# Arm_Board.net
KiCad netlist of a schematic drawn in EAGLE
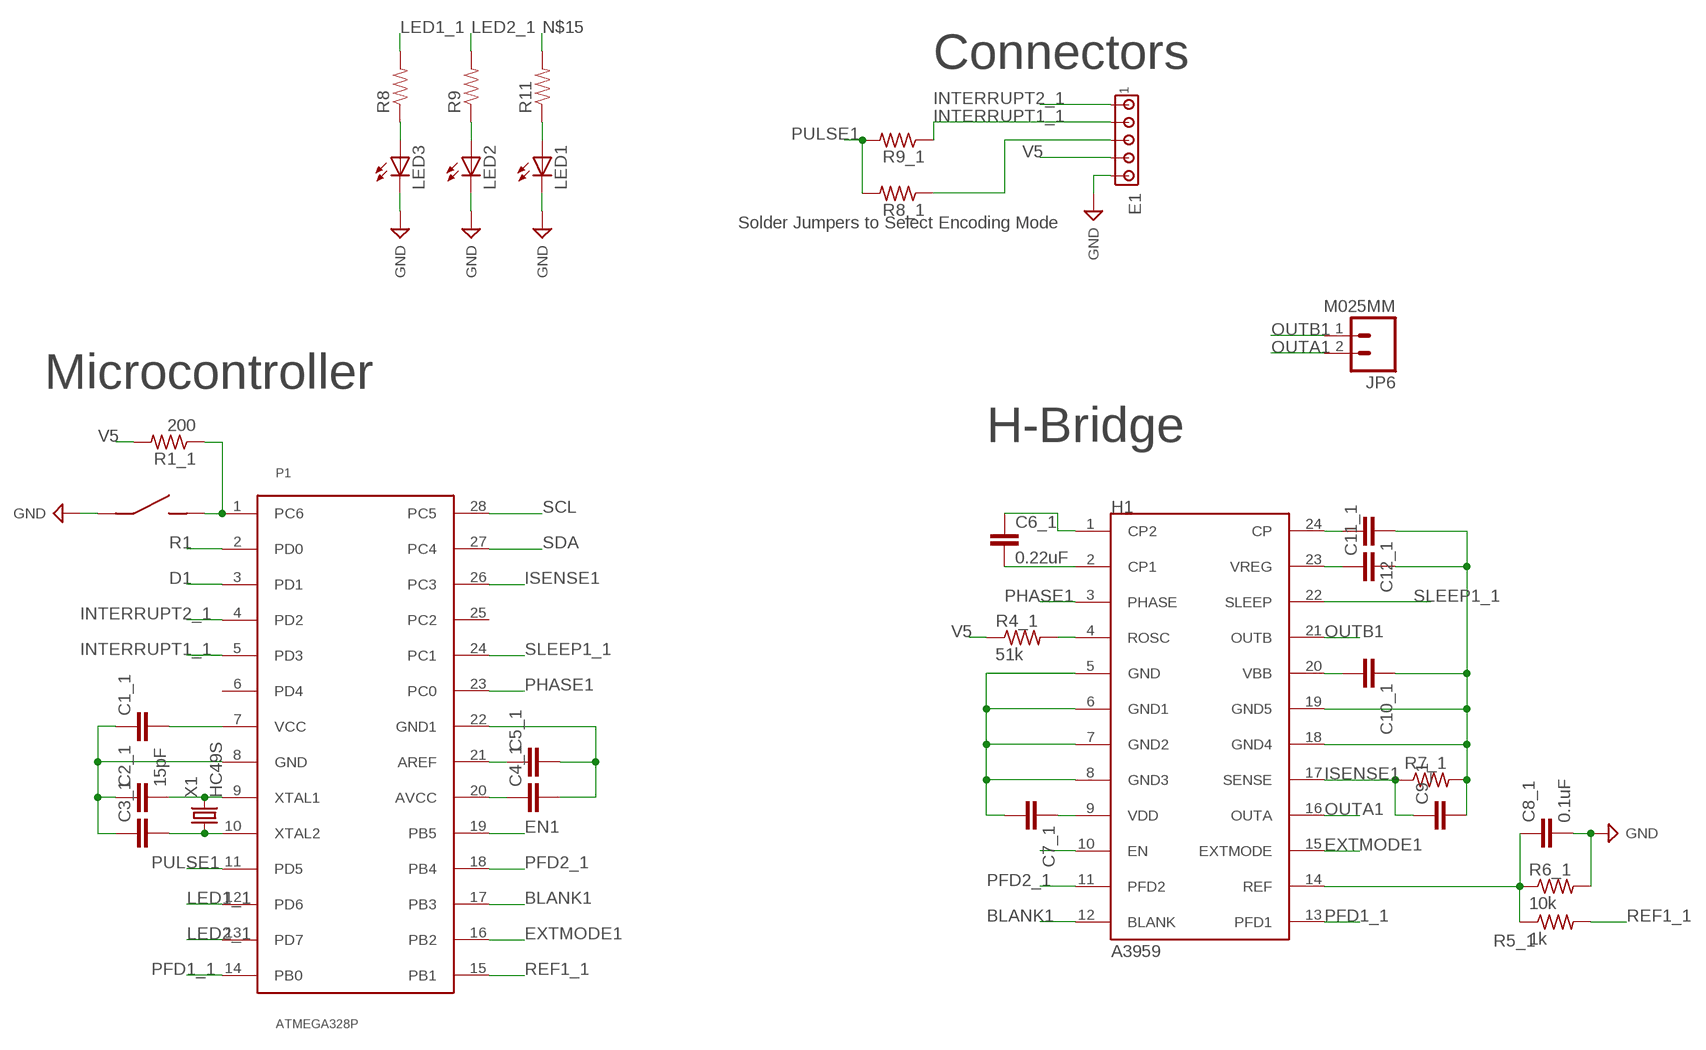
[diagram p0: schematic, sheet 1]
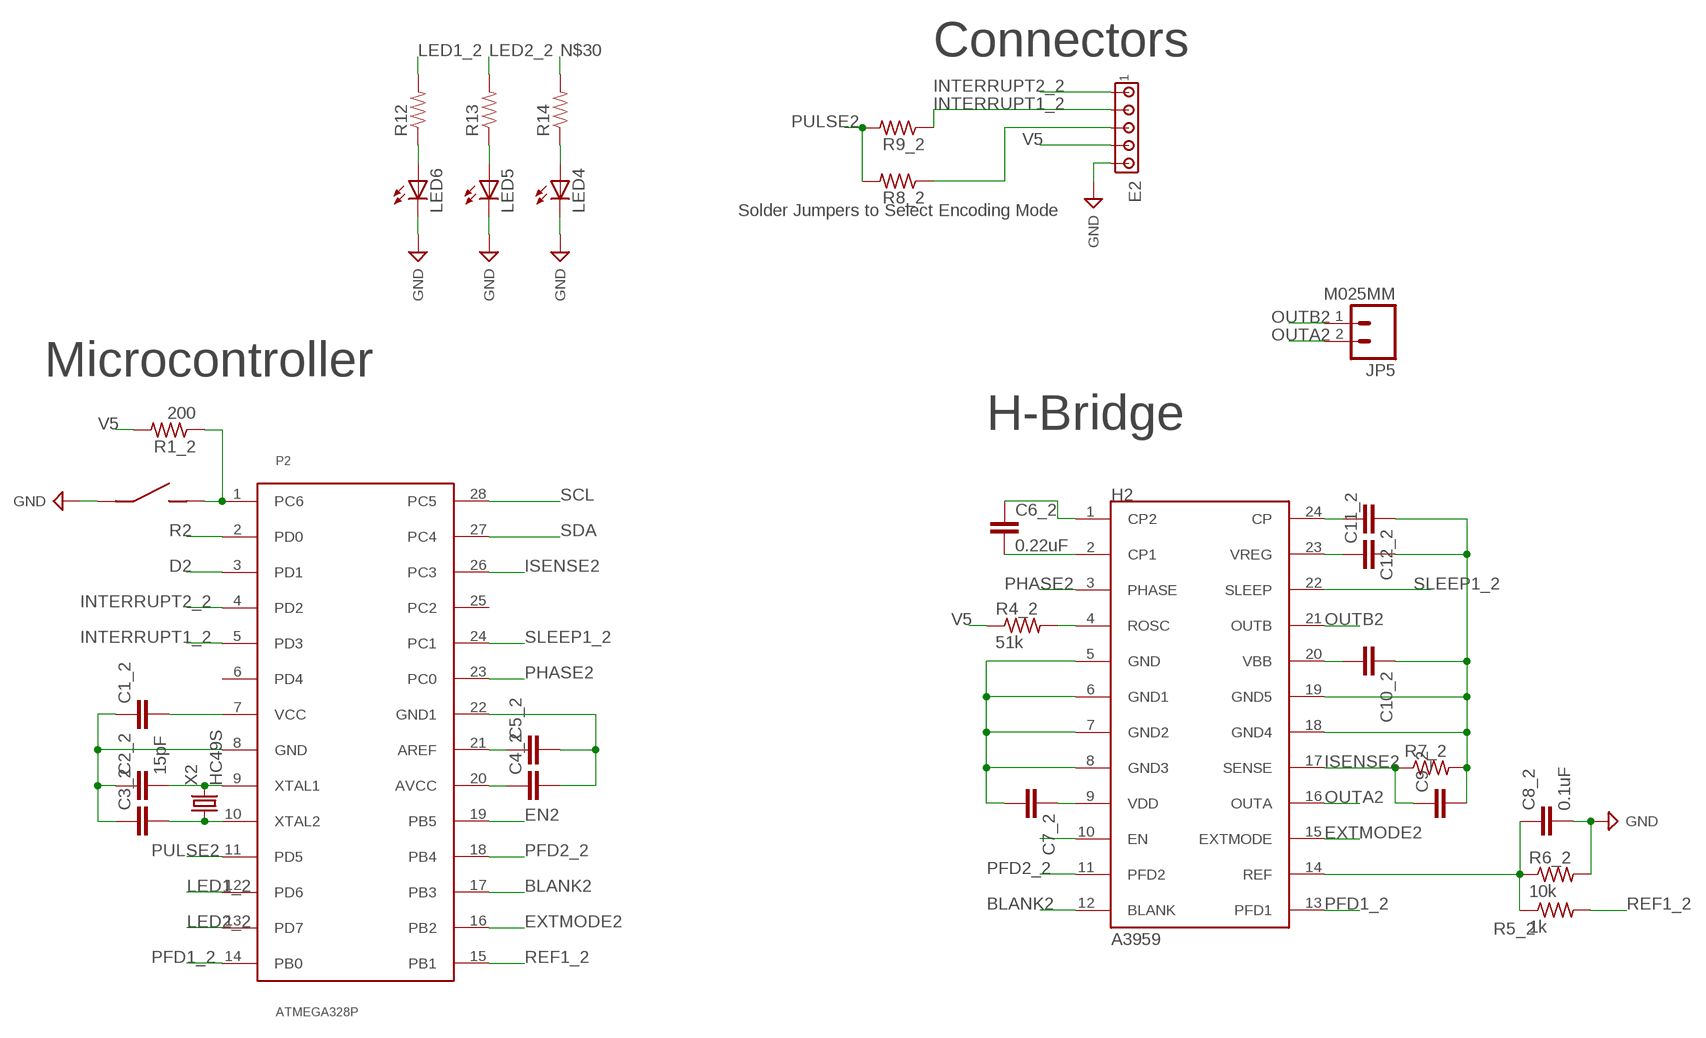
[diagram p1: schematic, sheet 2]
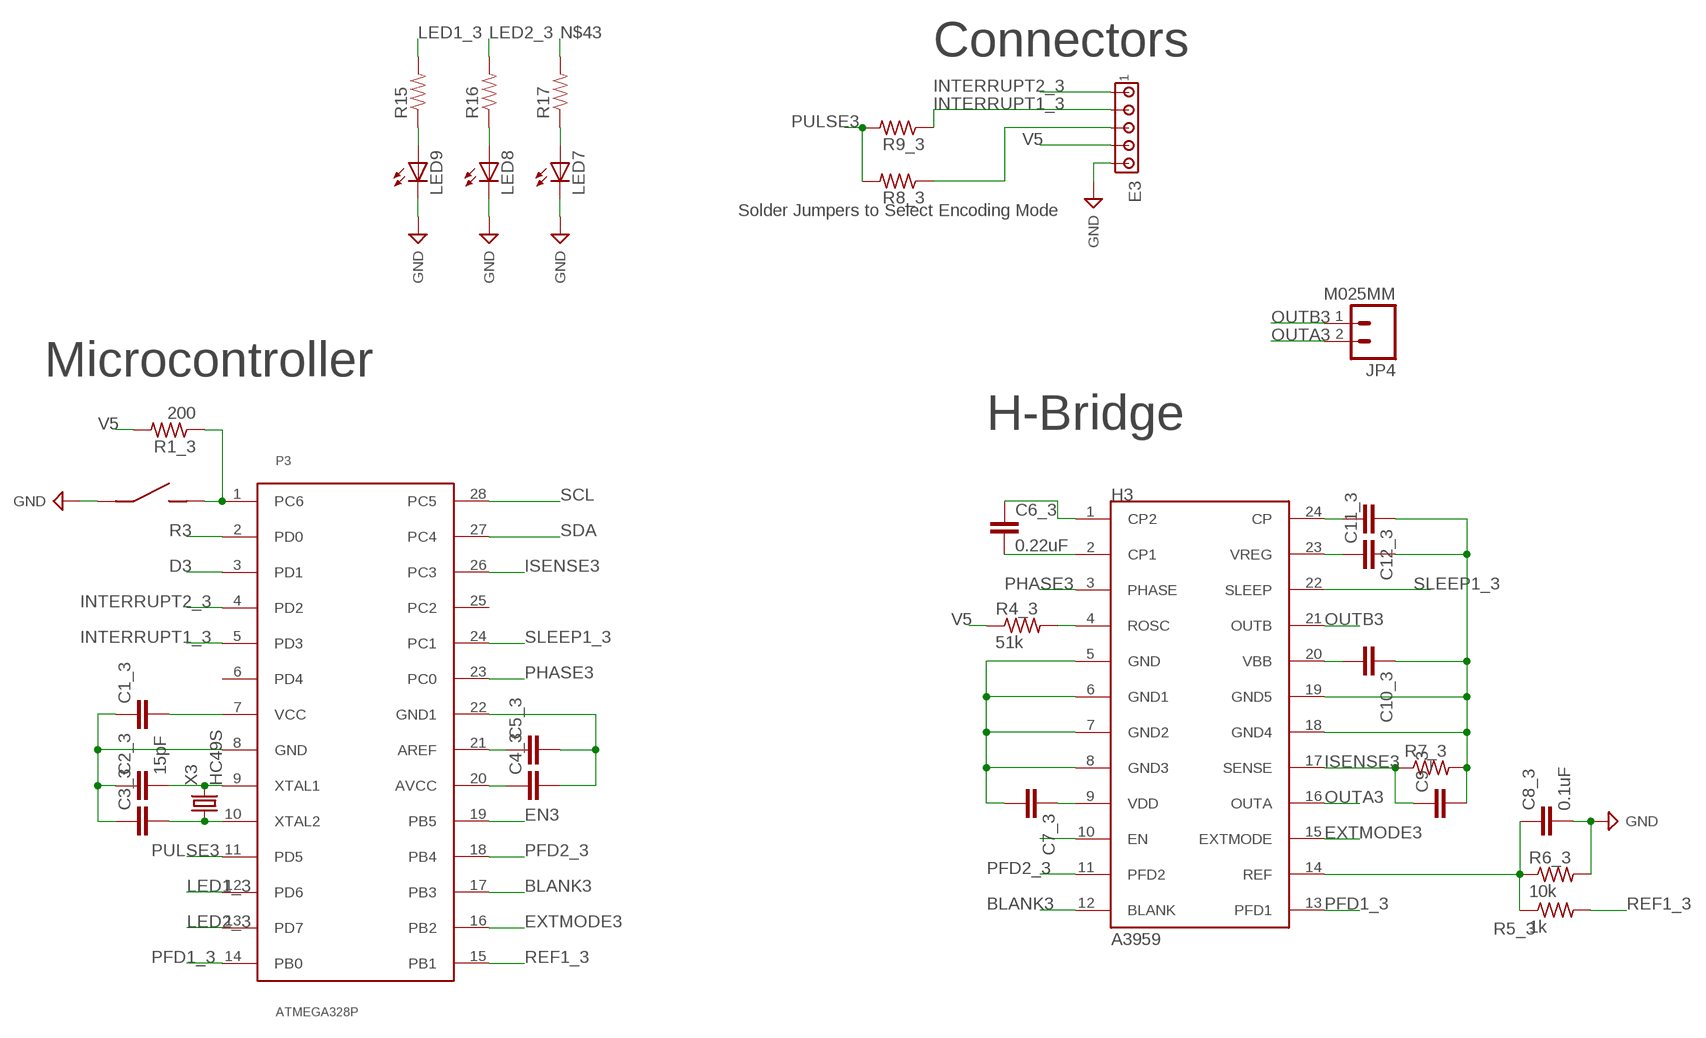
[diagram p2: schematic, sheet 3]
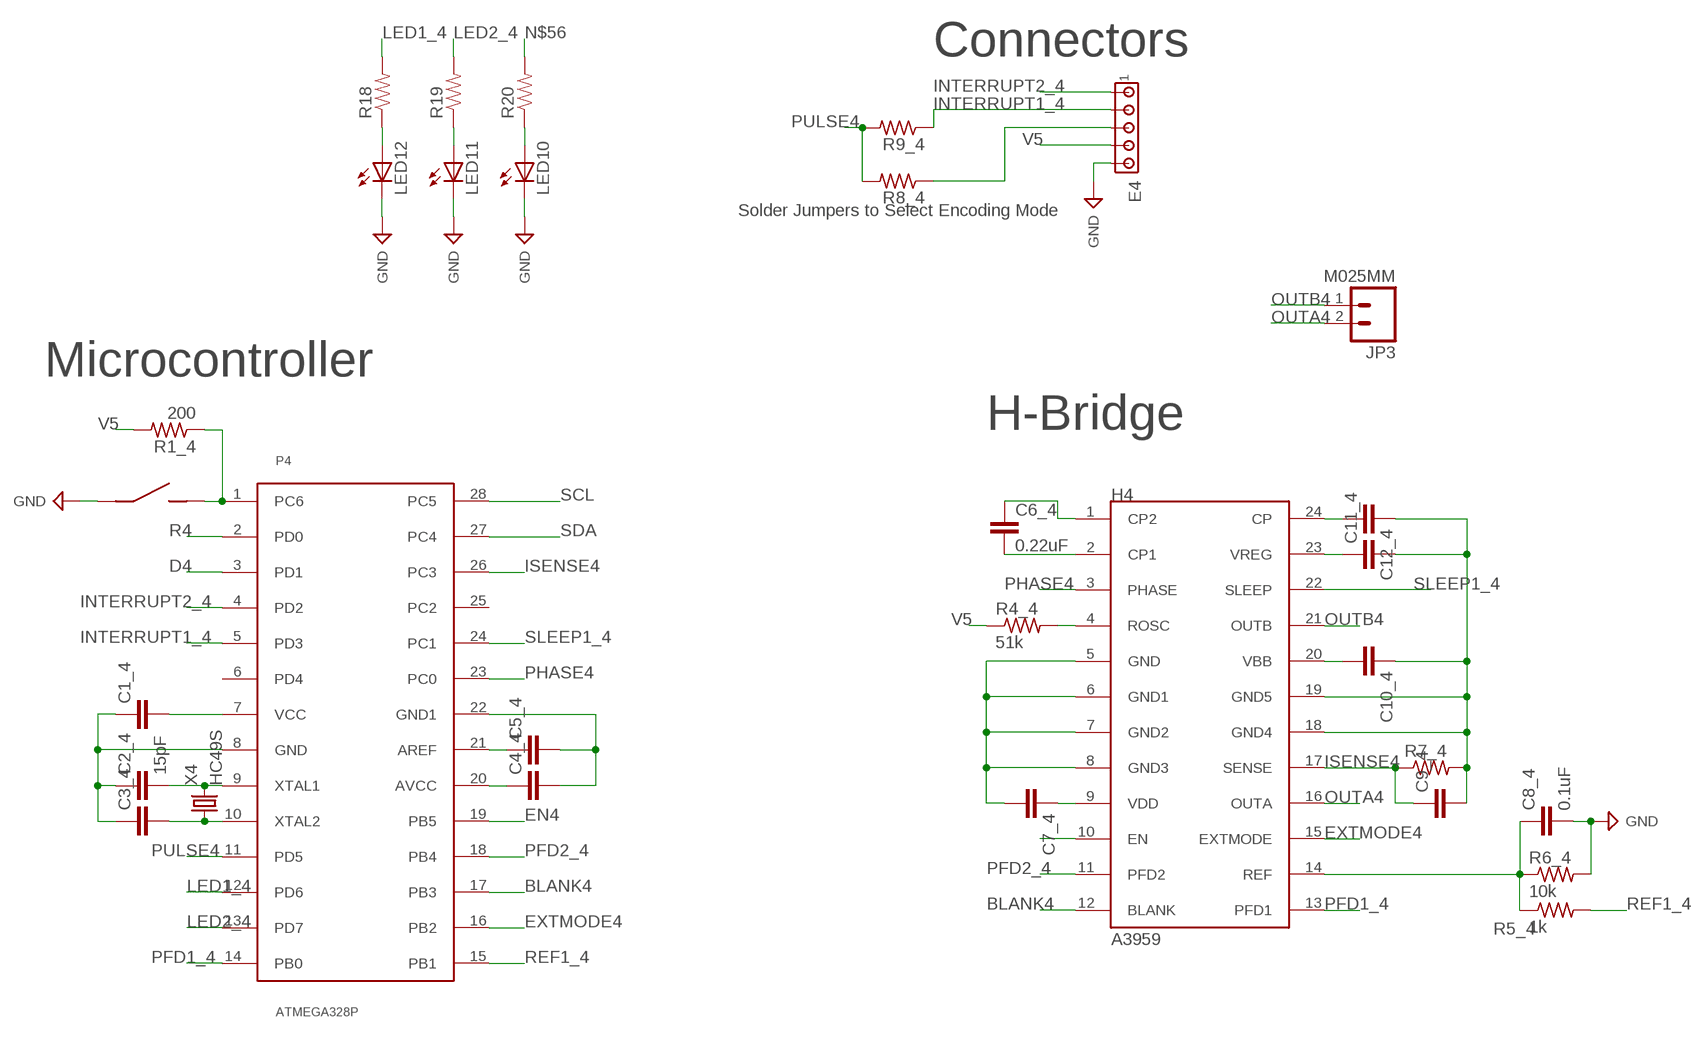
[diagram p3: schematic, sheet 4]
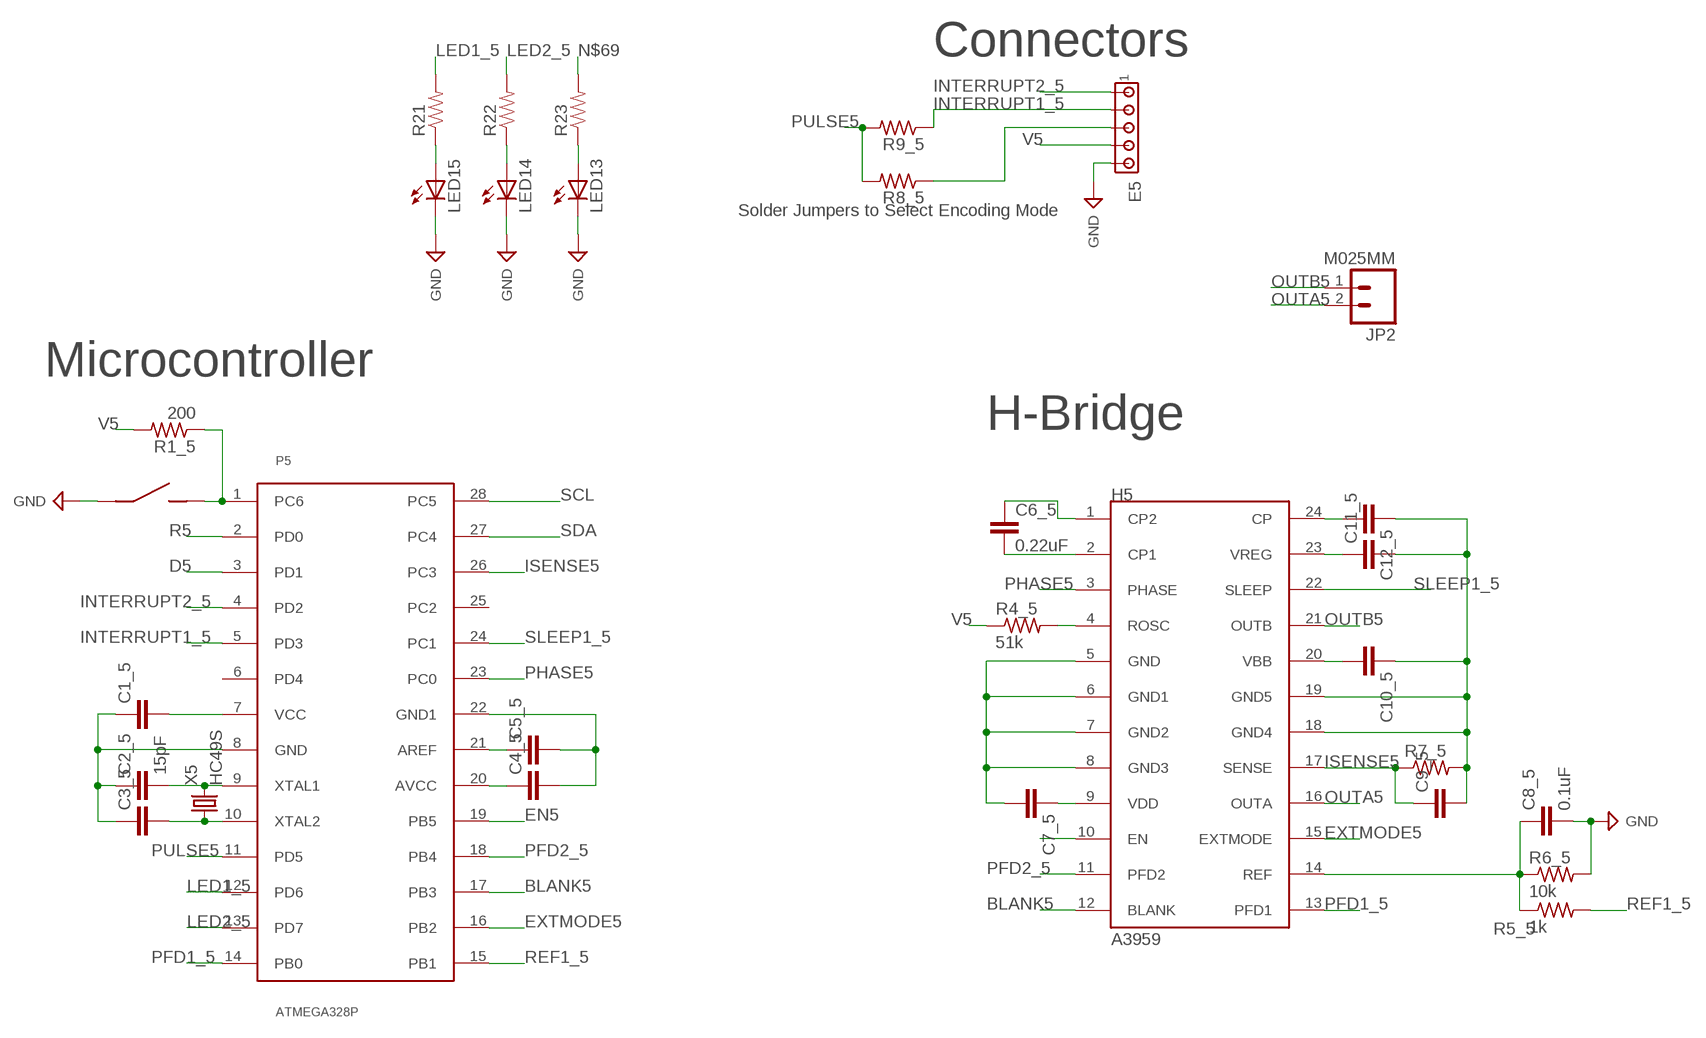
[diagram p4: schematic, sheet 5]
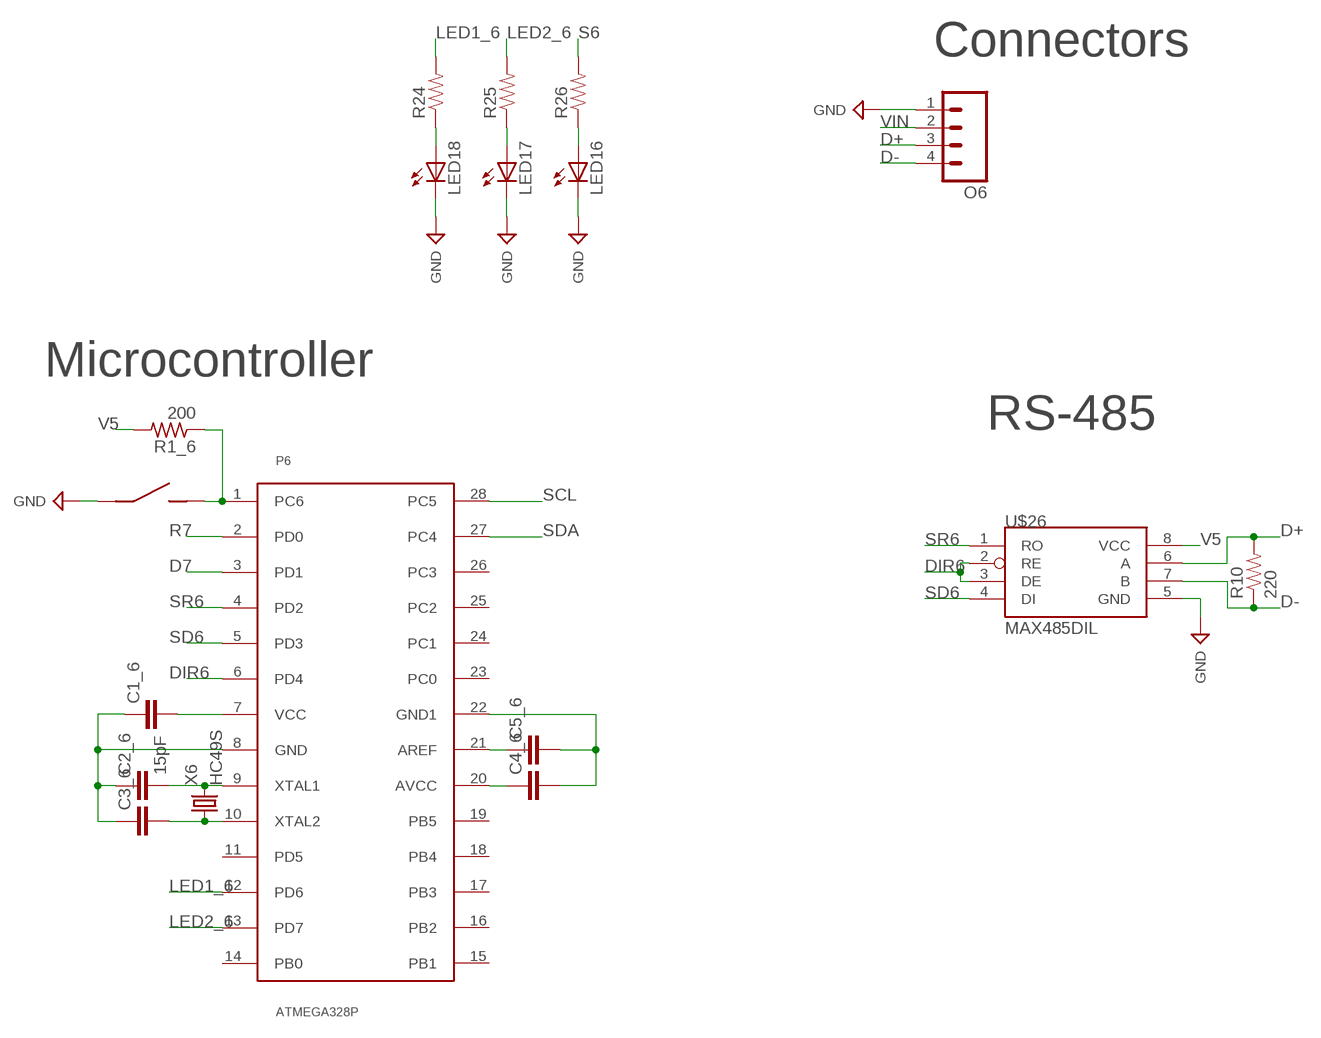
[diagram p5: schematic, sheet 6]
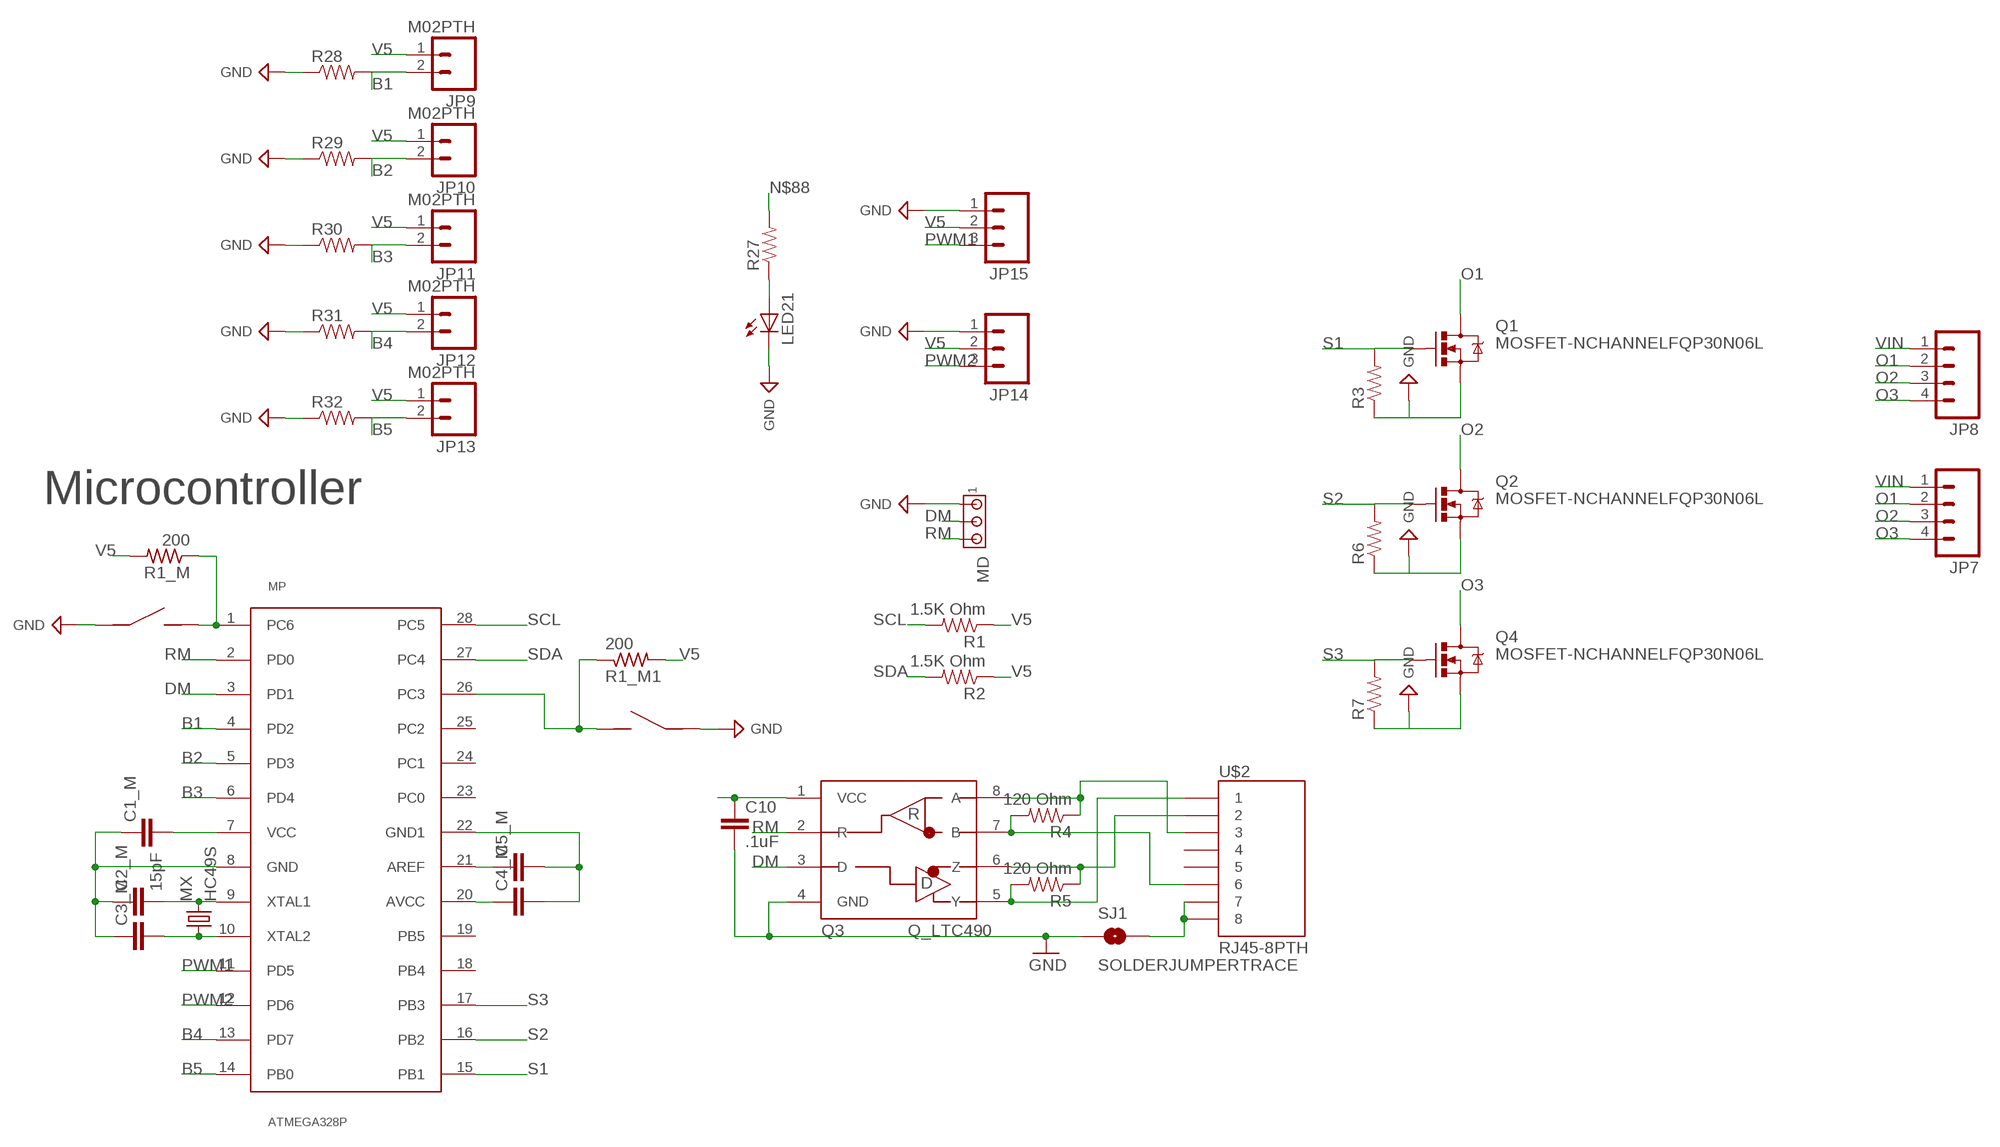
[diagram p6: schematic, sheet 7]
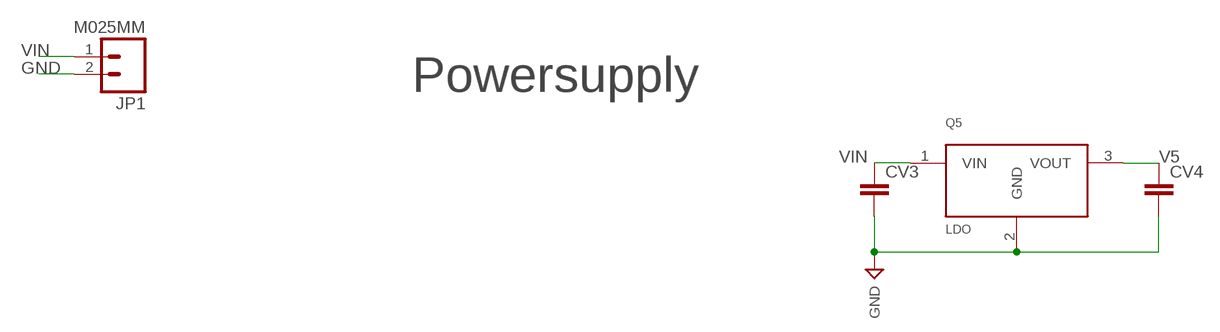
[diagram p7: schematic, sheet 8]

(export (version "E")
  (design (tool "Eeschema 10.0.6"))
  (components
    (comp (ref "C1_M")
      (value "C_CAP_0805")
      (footprint "eagle-import:C_0805")
      (libsource (lib "eagle-import") (part "C_CAP_0805"))
    )
    (comp (ref "C2_M")
      (value "15pF")
      (footprint "eagle-import:C_0805")
      (libsource (lib "eagle-import") (part "C_CAP_0805"))
    )
    (comp (ref "C3_M")
      (value "C_CAP_0805")
      (footprint "eagle-import:C_0805")
      (libsource (lib "eagle-import") (part "C_CAP_0805"))
    )
    (comp (ref "C4_M")
      (value "C_CAP_0805")
      (footprint "eagle-import:C_0805")
      (libsource (lib "eagle-import") (part "C_CAP_0805"))
    )
    (comp (ref "C5_M")
      (value "C_CAP_0805")
      (footprint "eagle-import:C_0805")
      (libsource (lib "eagle-import") (part "C_CAP_0805"))
    )
    (comp (ref "C10")
      (value ".1uF")
      (footprint "eagle-import:CAP-PTH-SMALL-KIT")
      (libsource (lib "eagle-import") (part "CAPKIT"))
    )
    (comp (ref "JP7")
      (value "M041X04_NO_SILK")
      (footprint "eagle-import:1X04_NO_SILK")
      (libsource (lib "eagle-import") (part "M041X04_NO_SILK"))
    )
    (comp (ref "JP8")
      (value "M041X04_NO_SILK")
      (footprint "eagle-import:1X04_NO_SILK")
      (libsource (lib "eagle-import") (part "M041X04_NO_SILK"))
    )
    (comp (ref "JP9")
      (value "M02PTH")
      (footprint "eagle-import:1X02")
      (libsource (lib "eagle-import") (part "M02PTH"))
    )
    (comp (ref "JP10")
      (value "M02PTH")
      (footprint "eagle-import:1X02")
      (libsource (lib "eagle-import") (part "M02PTH"))
    )
    (comp (ref "JP11")
      (value "M02PTH")
      (footprint "eagle-import:1X02")
      (libsource (lib "eagle-import") (part "M02PTH"))
    )
    (comp (ref "JP12")
      (value "M02PTH")
      (footprint "eagle-import:1X02")
      (libsource (lib "eagle-import") (part "M02PTH"))
    )
    (comp (ref "JP13")
      (value "M02PTH")
      (footprint "eagle-import:1X02")
      (libsource (lib "eagle-import") (part "M02PTH"))
    )
    (comp (ref "JP14")
      (value "M03PTH")
      (footprint "eagle-import:1X03")
      (libsource (lib "eagle-import") (part "M03PTH"))
    )
    (comp (ref "JP15")
      (value "M03PTH")
      (footprint "eagle-import:1X03")
      (libsource (lib "eagle-import") (part "M03PTH"))
    )
    (comp (ref "LED21")
      (value "LED1206")
      (footprint "eagle-import:LED-1206")
      (libsource (lib "eagle-import") (part "LED1206"))
    )
    (comp (ref "MD")
      (value "J_MTA3P_100")
      (footprint "eagle-import:J_MTA100_3P")
      (libsource (lib "eagle-import") (part "J_MTA3P_100"))
    )
    (comp (ref "MP")
      (value "ATMEGA328P")
      (footprint "eagle-import:DIP28")
      (libsource (lib "eagle-import") (part "Q_ATMEGA328P"))
    )
    (comp (ref "MS")
      (value "J_MC32857")
      (footprint "eagle-import:J_TOGGLE")
      (libsource (lib "eagle-import") (part "J_MC32857"))
    )
    (comp (ref "MS1")
      (value "J_MC32857")
      (footprint "eagle-import:J_TOGGLE")
      (libsource (lib "eagle-import") (part "J_MC32857"))
    )
    (comp (ref "MX")
      (value "HC49S")
      (footprint "eagle-import:HC-49")
      (libsource (lib "eagle-import") (part "X_HC49SCRYSTAL"))
    )
    (comp (ref "Q1")
      (value "MOSFET-NCHANNELFQP30N06L")
      (footprint "eagle-import:TO220V")
      (libsource (lib "eagle-import") (part "MOSFET-NCHANNELFQP30N06L"))
    )
    (comp (ref "Q2")
      (value "MOSFET-NCHANNELFQP30N06L")
      (footprint "eagle-import:TO220V")
      (libsource (lib "eagle-import") (part "MOSFET-NCHANNELFQP30N06L"))
    )
    (comp (ref "Q3")
      (value "Q_LTC490")
      (footprint "eagle-import:DIP8")
      (libsource (lib "eagle-import") (part "Q_LTC490"))
    )
    (comp (ref "Q4")
      (value "MOSFET-NCHANNELFQP30N06L")
      (footprint "eagle-import:TO220V")
      (libsource (lib "eagle-import") (part "MOSFET-NCHANNELFQP30N06L"))
    )
    (comp (ref "R1")
      (value "1.5K Ohm")
      (footprint "eagle-import:AXIAL-0.3")
      (libsource (lib "eagle-import") (part "RESISTORAXIAL-0.3"))
    )
    (comp (ref "R1_M")
      (value "200")
      (footprint "eagle-import:R_0805")
      (libsource (lib "eagle-import") (part "R_RES_0805"))
    )
    (comp (ref "R1_M1")
      (value "200")
      (footprint "eagle-import:R_0805")
      (libsource (lib "eagle-import") (part "R_RES_0805"))
    )
    (comp (ref "R2")
      (value "1.5K Ohm")
      (footprint "eagle-import:AXIAL-0.3")
      (libsource (lib "eagle-import") (part "RESISTORAXIAL-0.3"))
    )
    (comp (ref "R3")
      (value "10KOHM1/6W5%(PTH)KIT")
      (footprint "eagle-import:AXIAL-0.3-KIT")
      (libsource (lib "eagle-import") (part "10KOHM1/6W5%(PTH)KIT"))
    )
    (comp (ref "R4")
      (value "120 Ohm")
      (footprint "eagle-import:AXIAL-0.3")
      (libsource (lib "eagle-import") (part "RESISTORAXIAL-0.3"))
    )
    (comp (ref "R5")
      (value "120 Ohm")
      (footprint "eagle-import:AXIAL-0.3")
      (libsource (lib "eagle-import") (part "RESISTORAXIAL-0.3"))
    )
    (comp (ref "R6")
      (value "10KOHM1/6W5%(PTH)KIT")
      (footprint "eagle-import:AXIAL-0.3-KIT")
      (libsource (lib "eagle-import") (part "10KOHM1/6W5%(PTH)KIT"))
    )
    (comp (ref "R7")
      (value "10KOHM1/6W5%(PTH)KIT")
      (footprint "eagle-import:AXIAL-0.3-KIT")
      (libsource (lib "eagle-import") (part "10KOHM1/6W5%(PTH)KIT"))
    )
    (comp (ref "R27")
      (value "RESISTOR1206")
      (footprint "eagle-import:1206")
      (libsource (lib "eagle-import") (part "RESISTOR1206"))
    )
    (comp (ref "R28")
      (value "RESISTORPTH-1/6W")
      (footprint "eagle-import:1_6W-RES")
      (libsource (lib "eagle-import") (part "RESISTORPTH-1/6W"))
    )
    (comp (ref "R29")
      (value "RESISTORPTH-1/6W")
      (footprint "eagle-import:1_6W-RES")
      (libsource (lib "eagle-import") (part "RESISTORPTH-1/6W"))
    )
    (comp (ref "R30")
      (value "RESISTORPTH-1/6W")
      (footprint "eagle-import:1_6W-RES")
      (libsource (lib "eagle-import") (part "RESISTORPTH-1/6W"))
    )
    (comp (ref "R31")
      (value "RESISTORPTH-1/6W")
      (footprint "eagle-import:1_6W-RES")
      (libsource (lib "eagle-import") (part "RESISTORPTH-1/6W"))
    )
    (comp (ref "R32")
      (value "RESISTORPTH-1/6W")
      (footprint "eagle-import:1_6W-RES")
      (libsource (lib "eagle-import") (part "RESISTORPTH-1/6W"))
    )
    (comp (ref "SJ1")
      (value "SOLDERJUMPERTRACE")
      (footprint "eagle-import:SJ_2S-TRACE")
      (libsource (lib "eagle-import") (part "SOLDERJUMPERTRACE"))
    )
    (comp (ref "U$2")
      (value "RJ45-8PTH")
      (footprint "eagle-import:RJ45-8")
      (libsource (lib "eagle-import") (part "RJ45-8PTH"))
    )
    (comp (ref "C1_1")
      (value "C_CAP_0805")
      (footprint "eagle-import:C_0805")
      (libsource (lib "eagle-import") (part "C_CAP_0805"))
    )
    (comp (ref "C2_1")
      (value "15pF")
      (footprint "eagle-import:C_0805")
      (libsource (lib "eagle-import") (part "C_CAP_0805"))
    )
    (comp (ref "C3_1")
      (value "C_CAP_0805")
      (footprint "eagle-import:C_0805")
      (libsource (lib "eagle-import") (part "C_CAP_0805"))
    )
    (comp (ref "C4_1")
      (value "C_CAP_0805")
      (footprint "eagle-import:C_0805")
      (libsource (lib "eagle-import") (part "C_CAP_0805"))
    )
    (comp (ref "C5_1")
      (value "C_CAP_0805")
      (footprint "eagle-import:C_0805")
      (libsource (lib "eagle-import") (part "C_CAP_0805"))
    )
    (comp (ref "C6_1")
      (value "0.22uF")
      (footprint "eagle-import:C_0805")
      (libsource (lib "eagle-import") (part "C_CAP_0805"))
    )
    (comp (ref "C7_1")
      (value "C_CAP_0805")
      (footprint "eagle-import:C_0805")
      (libsource (lib "eagle-import") (part "C_CAP_0805"))
    )
    (comp (ref "C8_1")
      (value "0.1uF")
      (footprint "eagle-import:C_0805")
      (libsource (lib "eagle-import") (part "C_CAP_0805"))
    )
    (comp (ref "C9_1")
      (value "C_CAP_0805")
      (footprint "eagle-import:C_0805")
      (libsource (lib "eagle-import") (part "C_CAP_0805"))
    )
    (comp (ref "C10_1")
      (value "C_CAP_0805")
      (footprint "eagle-import:C_0805")
      (libsource (lib "eagle-import") (part "C_CAP_0805"))
    )
    (comp (ref "C11_1")
      (value "C_CAP_0805")
      (footprint "eagle-import:C_0805")
      (libsource (lib "eagle-import") (part "C_CAP_0805"))
    )
    (comp (ref "C12_1")
      (value "C_CAP_0805")
      (footprint "eagle-import:C_0805")
      (libsource (lib "eagle-import") (part "C_CAP_0805"))
    )
    (comp (ref "E1")
      (value "J_MTA5P_100")
      (footprint "eagle-import:J_MTA100_5P")
      (libsource (lib "eagle-import") (part "J_MTA5P_100"))
    )
    (comp (ref "H1")
      (value "A3959")
      (footprint "eagle-import:DIP24")
      (libsource (lib "eagle-import") (part "Q_A3959"))
    )
    (comp (ref "JP6")
      (value "M025MM")
      (footprint "eagle-import:SCREWTERMINAL-5MM-2")
      (libsource (lib "eagle-import") (part "M025MM"))
    )
    (comp (ref "LED1")
      (value "LED1206")
      (footprint "eagle-import:LED-1206")
      (libsource (lib "eagle-import") (part "LED1206"))
    )
    (comp (ref "LED2")
      (value "LED1206")
      (footprint "eagle-import:LED-1206")
      (libsource (lib "eagle-import") (part "LED1206"))
    )
    (comp (ref "LED3")
      (value "LED1206")
      (footprint "eagle-import:LED-1206")
      (libsource (lib "eagle-import") (part "LED1206"))
    )
    (comp (ref "P1")
      (value "ATMEGA328P")
      (footprint "eagle-import:DIP28")
      (libsource (lib "eagle-import") (part "Q_ATMEGA328P"))
    )
    (comp (ref "R1_1")
      (value "200")
      (footprint "eagle-import:R_0805")
      (libsource (lib "eagle-import") (part "R_RES_0805"))
    )
    (comp (ref "R4_1")
      (value "51k")
      (footprint "eagle-import:R_0805")
      (libsource (lib "eagle-import") (part "R_RES_0805"))
    )
    (comp (ref "R5_1")
      (value "1k")
      (footprint "eagle-import:R_0805")
      (libsource (lib "eagle-import") (part "R_RES_0805"))
    )
    (comp (ref "R6_1")
      (value "10k")
      (footprint "eagle-import:R_0805")
      (libsource (lib "eagle-import") (part "R_RES_0805"))
    )
    (comp (ref "R7_1")
      (value "R_RES_2010")
      (footprint "eagle-import:R_2010")
      (libsource (lib "eagle-import") (part "R_RES_2010"))
    )
    (comp (ref "R8")
      (value "RESISTOR1206")
      (footprint "eagle-import:1206")
      (libsource (lib "eagle-import") (part "RESISTOR1206"))
    )
    (comp (ref "R8_1")
      (value "R_RES_0603")
      (footprint "eagle-import:R_0603")
      (libsource (lib "eagle-import") (part "R_RES_0603"))
    )
    (comp (ref "R9")
      (value "RESISTOR1206")
      (footprint "eagle-import:1206")
      (libsource (lib "eagle-import") (part "RESISTOR1206"))
    )
    (comp (ref "R9_1")
      (value "R_RES_0603")
      (footprint "eagle-import:R_0603")
      (libsource (lib "eagle-import") (part "R_RES_0603"))
    )
    (comp (ref "R11")
      (value "RESISTOR1206")
      (footprint "eagle-import:1206")
      (libsource (lib "eagle-import") (part "RESISTOR1206"))
    )
    (comp (ref "S1")
      (value "J_MC32857")
      (footprint "eagle-import:J_TOGGLE")
      (libsource (lib "eagle-import") (part "J_MC32857"))
    )
    (comp (ref "X1")
      (value "HC49S")
      (footprint "eagle-import:HC-49")
      (libsource (lib "eagle-import") (part "X_HC49SCRYSTAL"))
    )
    (comp (ref "C1_2")
      (value "C_CAP_0805")
      (footprint "eagle-import:C_0805")
      (libsource (lib "eagle-import") (part "C_CAP_0805"))
    )
    (comp (ref "C2_2")
      (value "15pF")
      (footprint "eagle-import:C_0805")
      (libsource (lib "eagle-import") (part "C_CAP_0805"))
    )
    (comp (ref "C3_2")
      (value "C_CAP_0805")
      (footprint "eagle-import:C_0805")
      (libsource (lib "eagle-import") (part "C_CAP_0805"))
    )
    (comp (ref "C4_2")
      (value "C_CAP_0805")
      (footprint "eagle-import:C_0805")
      (libsource (lib "eagle-import") (part "C_CAP_0805"))
    )
    (comp (ref "C5_2")
      (value "C_CAP_0805")
      (footprint "eagle-import:C_0805")
      (libsource (lib "eagle-import") (part "C_CAP_0805"))
    )
    (comp (ref "C6_2")
      (value "0.22uF")
      (footprint "eagle-import:C_0805")
      (libsource (lib "eagle-import") (part "C_CAP_0805"))
    )
    (comp (ref "C7_2")
      (value "C_CAP_0805")
      (footprint "eagle-import:C_0805")
      (libsource (lib "eagle-import") (part "C_CAP_0805"))
    )
    (comp (ref "C8_2")
      (value "0.1uF")
      (footprint "eagle-import:C_0805")
      (libsource (lib "eagle-import") (part "C_CAP_0805"))
    )
    (comp (ref "C9_2")
      (value "C_CAP_0805")
      (footprint "eagle-import:C_0805")
      (libsource (lib "eagle-import") (part "C_CAP_0805"))
    )
    (comp (ref "C10_2")
      (value "C_CAP_0805")
      (footprint "eagle-import:C_0805")
      (libsource (lib "eagle-import") (part "C_CAP_0805"))
    )
    (comp (ref "C11_2")
      (value "C_CAP_0805")
      (footprint "eagle-import:C_0805")
      (libsource (lib "eagle-import") (part "C_CAP_0805"))
    )
    (comp (ref "C12_2")
      (value "C_CAP_0805")
      (footprint "eagle-import:C_0805")
      (libsource (lib "eagle-import") (part "C_CAP_0805"))
    )
    (comp (ref "E2")
      (value "J_MTA5P_100")
      (footprint "eagle-import:J_MTA100_5P")
      (libsource (lib "eagle-import") (part "J_MTA5P_100"))
    )
    (comp (ref "H2")
      (value "A3959")
      (footprint "eagle-import:DIP24")
      (libsource (lib "eagle-import") (part "Q_A3959"))
    )
    (comp (ref "JP5")
      (value "M025MM")
      (footprint "eagle-import:SCREWTERMINAL-5MM-2")
      (libsource (lib "eagle-import") (part "M025MM"))
    )
    (comp (ref "LED4")
      (value "LED1206")
      (footprint "eagle-import:LED-1206")
      (libsource (lib "eagle-import") (part "LED1206"))
    )
    (comp (ref "LED5")
      (value "LED1206")
      (footprint "eagle-import:LED-1206")
      (libsource (lib "eagle-import") (part "LED1206"))
    )
    (comp (ref "LED6")
      (value "LED1206")
      (footprint "eagle-import:LED-1206")
      (libsource (lib "eagle-import") (part "LED1206"))
    )
    (comp (ref "P2")
      (value "ATMEGA328P")
      (footprint "eagle-import:DIP28")
      (libsource (lib "eagle-import") (part "Q_ATMEGA328P"))
    )
    (comp (ref "R1_2")
      (value "200")
      (footprint "eagle-import:R_0805")
      (libsource (lib "eagle-import") (part "R_RES_0805"))
    )
    (comp (ref "R4_2")
      (value "51k")
      (footprint "eagle-import:R_0805")
      (libsource (lib "eagle-import") (part "R_RES_0805"))
    )
    (comp (ref "R5_2")
      (value "1k")
      (footprint "eagle-import:R_0805")
      (libsource (lib "eagle-import") (part "R_RES_0805"))
    )
    (comp (ref "R6_2")
      (value "10k")
      (footprint "eagle-import:R_0805")
      (libsource (lib "eagle-import") (part "R_RES_0805"))
    )
    (comp (ref "R7_2")
      (value "R_RES_2010")
      (footprint "eagle-import:R_2010")
      (libsource (lib "eagle-import") (part "R_RES_2010"))
    )
    (comp (ref "R8_2")
      (value "R_RES_0603")
      (footprint "eagle-import:R_0603")
      (libsource (lib "eagle-import") (part "R_RES_0603"))
    )
    (comp (ref "R9_2")
      (value "R_RES_0603")
      (footprint "eagle-import:R_0603")
      (libsource (lib "eagle-import") (part "R_RES_0603"))
    )
    (comp (ref "R12")
      (value "RESISTOR1206")
      (footprint "eagle-import:1206")
      (libsource (lib "eagle-import") (part "RESISTOR1206"))
    )
    (comp (ref "R13")
      (value "RESISTOR1206")
      (footprint "eagle-import:1206")
      (libsource (lib "eagle-import") (part "RESISTOR1206"))
    )
    (comp (ref "R14")
      (value "RESISTOR1206")
      (footprint "eagle-import:1206")
      (libsource (lib "eagle-import") (part "RESISTOR1206"))
    )
    (comp (ref "S2")
      (value "J_MC32857")
      (footprint "eagle-import:J_TOGGLE")
      (libsource (lib "eagle-import") (part "J_MC32857"))
    )
    (comp (ref "X2")
      (value "HC49S")
      (footprint "eagle-import:HC-49")
      (libsource (lib "eagle-import") (part "X_HC49SCRYSTAL"))
    )
    (comp (ref "C1_5")
      (value "C_CAP_0805")
      (footprint "eagle-import:C_0805")
      (libsource (lib "eagle-import") (part "C_CAP_0805"))
    )
    (comp (ref "C2_5")
      (value "15pF")
      (footprint "eagle-import:C_0805")
      (libsource (lib "eagle-import") (part "C_CAP_0805"))
    )
    (comp (ref "C3_5")
      (value "C_CAP_0805")
      (footprint "eagle-import:C_0805")
      (libsource (lib "eagle-import") (part "C_CAP_0805"))
    )
    (comp (ref "C4_5")
      (value "C_CAP_0805")
      (footprint "eagle-import:C_0805")
      (libsource (lib "eagle-import") (part "C_CAP_0805"))
    )
    (comp (ref "C5_5")
      (value "C_CAP_0805")
      (footprint "eagle-import:C_0805")
      (libsource (lib "eagle-import") (part "C_CAP_0805"))
    )
    (comp (ref "C6_5")
      (value "0.22uF")
      (footprint "eagle-import:C_0805")
      (libsource (lib "eagle-import") (part "C_CAP_0805"))
    )
    (comp (ref "C7_5")
      (value "C_CAP_0805")
      (footprint "eagle-import:C_0805")
      (libsource (lib "eagle-import") (part "C_CAP_0805"))
    )
    (comp (ref "C8_5")
      (value "0.1uF")
      (footprint "eagle-import:C_0805")
      (libsource (lib "eagle-import") (part "C_CAP_0805"))
    )
    (comp (ref "C9_5")
      (value "C_CAP_0805")
      (footprint "eagle-import:C_0805")
      (libsource (lib "eagle-import") (part "C_CAP_0805"))
    )
    (comp (ref "C10_5")
      (value "C_CAP_0805")
      (footprint "eagle-import:C_0805")
      (libsource (lib "eagle-import") (part "C_CAP_0805"))
    )
    (comp (ref "C11_5")
      (value "C_CAP_0805")
      (footprint "eagle-import:C_0805")
      (libsource (lib "eagle-import") (part "C_CAP_0805"))
    )
    (comp (ref "C12_5")
      (value "C_CAP_0805")
      (footprint "eagle-import:C_0805")
      (libsource (lib "eagle-import") (part "C_CAP_0805"))
    )
    (comp (ref "E5")
      (value "J_MTA5P_100")
      (footprint "eagle-import:J_MTA100_5P")
      (libsource (lib "eagle-import") (part "J_MTA5P_100"))
    )
    (comp (ref "H5")
      (value "A3959")
      (footprint "eagle-import:DIP24")
      (libsource (lib "eagle-import") (part "Q_A3959"))
    )
    (comp (ref "JP2")
      (value "M025MM")
      (footprint "eagle-import:SCREWTERMINAL-5MM-2")
      (libsource (lib "eagle-import") (part "M025MM"))
    )
    (comp (ref "LED13")
      (value "LED1206")
      (footprint "eagle-import:LED-1206")
      (libsource (lib "eagle-import") (part "LED1206"))
    )
    (comp (ref "LED14")
      (value "LED1206")
      (footprint "eagle-import:LED-1206")
      (libsource (lib "eagle-import") (part "LED1206"))
    )
    (comp (ref "LED15")
      (value "LED1206")
      (footprint "eagle-import:LED-1206")
      (libsource (lib "eagle-import") (part "LED1206"))
    )
    (comp (ref "P5")
      (value "ATMEGA328P")
      (footprint "eagle-import:DIP28")
      (libsource (lib "eagle-import") (part "Q_ATMEGA328P"))
    )
    (comp (ref "R1_5")
      (value "200")
      (footprint "eagle-import:R_0805")
      (libsource (lib "eagle-import") (part "R_RES_0805"))
    )
    (comp (ref "R4_5")
      (value "51k")
      (footprint "eagle-import:R_0805")
      (libsource (lib "eagle-import") (part "R_RES_0805"))
    )
    (comp (ref "R5_5")
      (value "1k")
      (footprint "eagle-import:R_0805")
      (libsource (lib "eagle-import") (part "R_RES_0805"))
    )
    (comp (ref "R6_5")
      (value "10k")
      (footprint "eagle-import:R_0805")
      (libsource (lib "eagle-import") (part "R_RES_0805"))
    )
    (comp (ref "R7_5")
      (value "R_RES_2010")
      (footprint "eagle-import:R_2010")
      (libsource (lib "eagle-import") (part "R_RES_2010"))
    )
    (comp (ref "R8_5")
      (value "R_RES_0603")
      (footprint "eagle-import:R_0603")
      (libsource (lib "eagle-import") (part "R_RES_0603"))
    )
    (comp (ref "R9_5")
      (value "R_RES_0603")
      (footprint "eagle-import:R_0603")
      (libsource (lib "eagle-import") (part "R_RES_0603"))
    )
    (comp (ref "R21")
      (value "RESISTOR1206")
      (footprint "eagle-import:1206")
      (libsource (lib "eagle-import") (part "RESISTOR1206"))
    )
    (comp (ref "R22")
      (value "RESISTOR1206")
      (footprint "eagle-import:1206")
      (libsource (lib "eagle-import") (part "RESISTOR1206"))
    )
    (comp (ref "R23")
      (value "RESISTOR1206")
      (footprint "eagle-import:1206")
      (libsource (lib "eagle-import") (part "RESISTOR1206"))
    )
    (comp (ref "S5")
      (value "J_MC32857")
      (footprint "eagle-import:J_TOGGLE")
      (libsource (lib "eagle-import") (part "J_MC32857"))
    )
    (comp (ref "X5")
      (value "HC49S")
      (footprint "eagle-import:HC-49")
      (libsource (lib "eagle-import") (part "X_HC49SCRYSTAL"))
    )
    (comp (ref "CV3")
      (value "C_CAP_0805")
      (footprint "eagle-import:C_0805")
      (libsource (lib "eagle-import") (part "C_CAP_0805"))
    )
    (comp (ref "CV4")
      (value "C_CAP_0805")
      (footprint "eagle-import:C_0805")
      (libsource (lib "eagle-import") (part "C_CAP_0805"))
    )
    (comp (ref "JP1")
      (value "M025MM")
      (footprint "eagle-import:SCREWTERMINAL-5MM-2")
      (libsource (lib "eagle-import") (part "M025MM"))
    )
    (comp (ref "Q5")
      (value "LDO")
      (footprint "eagle-import:TO-220")
      (libsource (lib "eagle-import") (part "Q_LDO"))
    )
    (comp (ref "C1_6")
      (value "C_CAP_0805")
      (footprint "eagle-import:C_0805")
      (libsource (lib "eagle-import") (part "C_CAP_0805"))
    )
    (comp (ref "C2_6")
      (value "15pF")
      (footprint "eagle-import:C_0805")
      (libsource (lib "eagle-import") (part "C_CAP_0805"))
    )
    (comp (ref "C3_6")
      (value "C_CAP_0805")
      (footprint "eagle-import:C_0805")
      (libsource (lib "eagle-import") (part "C_CAP_0805"))
    )
    (comp (ref "C4_6")
      (value "C_CAP_0805")
      (footprint "eagle-import:C_0805")
      (libsource (lib "eagle-import") (part "C_CAP_0805"))
    )
    (comp (ref "C5_6")
      (value "C_CAP_0805")
      (footprint "eagle-import:C_0805")
      (libsource (lib "eagle-import") (part "C_CAP_0805"))
    )
    (comp (ref "J6")
      (value "J_MC32857")
      (footprint "eagle-import:J_TOGGLE")
      (libsource (lib "eagle-import") (part "J_MC32857"))
    )
    (comp (ref "LED16")
      (value "LED1206")
      (footprint "eagle-import:LED-1206")
      (libsource (lib "eagle-import") (part "LED1206"))
    )
    (comp (ref "LED17")
      (value "LED1206")
      (footprint "eagle-import:LED-1206")
      (libsource (lib "eagle-import") (part "LED1206"))
    )
    (comp (ref "LED18")
      (value "LED1206")
      (footprint "eagle-import:LED-1206")
      (libsource (lib "eagle-import") (part "LED1206"))
    )
    (comp (ref "O6")
      (value "M041X04_NO_SILK")
      (footprint "eagle-import:1X04_NO_SILK")
      (libsource (lib "eagle-import") (part "M041X04_NO_SILK"))
    )
    (comp (ref "P6")
      (value "ATMEGA328P")
      (footprint "eagle-import:DIP28")
      (libsource (lib "eagle-import") (part "Q_ATMEGA328P"))
    )
    (comp (ref "R1_6")
      (value "200")
      (footprint "eagle-import:R_0805")
      (libsource (lib "eagle-import") (part "R_RES_0805"))
    )
    (comp (ref "R10")
      (value "220")
      (footprint "eagle-import:AXIAL-0.3EZ")
      (libsource (lib "eagle-import") (part "RESISTOREZ"))
    )
    (comp (ref "R24")
      (value "RESISTOR1206")
      (footprint "eagle-import:1206")
      (libsource (lib "eagle-import") (part "RESISTOR1206"))
    )
    (comp (ref "R25")
      (value "RESISTOR1206")
      (footprint "eagle-import:1206")
      (libsource (lib "eagle-import") (part "RESISTOR1206"))
    )
    (comp (ref "R26")
      (value "RESISTOR1206")
      (footprint "eagle-import:1206")
      (libsource (lib "eagle-import") (part "RESISTOR1206"))
    )
    (comp (ref "U$26")
      (value "MAX485DIL")
      (footprint "eagle-import:DIL08")
      (libsource (lib "eagle-import") (part "MAX485DIL"))
    )
    (comp (ref "X6")
      (value "HC49S")
      (footprint "eagle-import:HC-49")
      (libsource (lib "eagle-import") (part "X_HC49SCRYSTAL"))
    )
    (comp (ref "C1_4")
      (value "C_CAP_0805")
      (footprint "eagle-import:C_0805")
      (libsource (lib "eagle-import") (part "C_CAP_0805"))
    )
    (comp (ref "C2_4")
      (value "15pF")
      (footprint "eagle-import:C_0805")
      (libsource (lib "eagle-import") (part "C_CAP_0805"))
    )
    (comp (ref "C3_4")
      (value "C_CAP_0805")
      (footprint "eagle-import:C_0805")
      (libsource (lib "eagle-import") (part "C_CAP_0805"))
    )
    (comp (ref "C4_4")
      (value "C_CAP_0805")
      (footprint "eagle-import:C_0805")
      (libsource (lib "eagle-import") (part "C_CAP_0805"))
    )
    (comp (ref "C5_4")
      (value "C_CAP_0805")
      (footprint "eagle-import:C_0805")
      (libsource (lib "eagle-import") (part "C_CAP_0805"))
    )
    (comp (ref "C6_4")
      (value "0.22uF")
      (footprint "eagle-import:C_0805")
      (libsource (lib "eagle-import") (part "C_CAP_0805"))
    )
    (comp (ref "C7_4")
      (value "C_CAP_0805")
      (footprint "eagle-import:C_0805")
      (libsource (lib "eagle-import") (part "C_CAP_0805"))
    )
    (comp (ref "C8_4")
      (value "0.1uF")
      (footprint "eagle-import:C_0805")
      (libsource (lib "eagle-import") (part "C_CAP_0805"))
    )
    (comp (ref "C9_4")
      (value "C_CAP_0805")
      (footprint "eagle-import:C_0805")
      (libsource (lib "eagle-import") (part "C_CAP_0805"))
    )
    (comp (ref "C10_4")
      (value "C_CAP_0805")
      (footprint "eagle-import:C_0805")
      (libsource (lib "eagle-import") (part "C_CAP_0805"))
    )
    (comp (ref "C11_4")
      (value "C_CAP_0805")
      (footprint "eagle-import:C_0805")
      (libsource (lib "eagle-import") (part "C_CAP_0805"))
    )
    (comp (ref "C12_4")
      (value "C_CAP_0805")
      (footprint "eagle-import:C_0805")
      (libsource (lib "eagle-import") (part "C_CAP_0805"))
    )
    (comp (ref "E4")
      (value "J_MTA5P_100")
      (footprint "eagle-import:J_MTA100_5P")
      (libsource (lib "eagle-import") (part "J_MTA5P_100"))
    )
    (comp (ref "H4")
      (value "A3959")
      (footprint "eagle-import:DIP24")
      (libsource (lib "eagle-import") (part "Q_A3959"))
    )
    (comp (ref "JP3")
      (value "M025MM")
      (footprint "eagle-import:SCREWTERMINAL-5MM-2")
      (libsource (lib "eagle-import") (part "M025MM"))
    )
    (comp (ref "LED10")
      (value "LED1206")
      (footprint "eagle-import:LED-1206")
      (libsource (lib "eagle-import") (part "LED1206"))
    )
    (comp (ref "LED11")
      (value "LED1206")
      (footprint "eagle-import:LED-1206")
      (libsource (lib "eagle-import") (part "LED1206"))
    )
    (comp (ref "LED12")
      (value "LED1206")
      (footprint "eagle-import:LED-1206")
      (libsource (lib "eagle-import") (part "LED1206"))
    )
    (comp (ref "P4")
      (value "ATMEGA328P")
      (footprint "eagle-import:DIP28")
      (libsource (lib "eagle-import") (part "Q_ATMEGA328P"))
    )
    (comp (ref "R1_4")
      (value "200")
      (footprint "eagle-import:R_0805")
      (libsource (lib "eagle-import") (part "R_RES_0805"))
    )
    (comp (ref "R4_4")
      (value "51k")
      (footprint "eagle-import:R_0805")
      (libsource (lib "eagle-import") (part "R_RES_0805"))
    )
    (comp (ref "R5_4")
      (value "1k")
      (footprint "eagle-import:R_0805")
      (libsource (lib "eagle-import") (part "R_RES_0805"))
    )
    (comp (ref "R6_4")
      (value "10k")
      (footprint "eagle-import:R_0805")
      (libsource (lib "eagle-import") (part "R_RES_0805"))
    )
    (comp (ref "R7_4")
      (value "R_RES_2010")
      (footprint "eagle-import:R_2010")
      (libsource (lib "eagle-import") (part "R_RES_2010"))
    )
    (comp (ref "R8_4")
      (value "R_RES_0603")
      (footprint "eagle-import:R_0603")
      (libsource (lib "eagle-import") (part "R_RES_0603"))
    )
    (comp (ref "R9_4")
      (value "R_RES_0603")
      (footprint "eagle-import:R_0603")
      (libsource (lib "eagle-import") (part "R_RES_0603"))
    )
    (comp (ref "R18")
      (value "RESISTOR1206")
      (footprint "eagle-import:1206")
      (libsource (lib "eagle-import") (part "RESISTOR1206"))
    )
    (comp (ref "R19")
      (value "RESISTOR1206")
      (footprint "eagle-import:1206")
      (libsource (lib "eagle-import") (part "RESISTOR1206"))
    )
    (comp (ref "R20")
      (value "RESISTOR1206")
      (footprint "eagle-import:1206")
      (libsource (lib "eagle-import") (part "RESISTOR1206"))
    )
    (comp (ref "S4")
      (value "J_MC32857")
      (footprint "eagle-import:J_TOGGLE")
      (libsource (lib "eagle-import") (part "J_MC32857"))
    )
    (comp (ref "X4")
      (value "HC49S")
      (footprint "eagle-import:HC-49")
      (libsource (lib "eagle-import") (part "X_HC49SCRYSTAL"))
    )
    (comp (ref "C1_3")
      (value "C_CAP_0805")
      (footprint "eagle-import:C_0805")
      (libsource (lib "eagle-import") (part "C_CAP_0805"))
    )
    (comp (ref "C2_3")
      (value "15pF")
      (footprint "eagle-import:C_0805")
      (libsource (lib "eagle-import") (part "C_CAP_0805"))
    )
    (comp (ref "C3_3")
      (value "C_CAP_0805")
      (footprint "eagle-import:C_0805")
      (libsource (lib "eagle-import") (part "C_CAP_0805"))
    )
    (comp (ref "C4_3")
      (value "C_CAP_0805")
      (footprint "eagle-import:C_0805")
      (libsource (lib "eagle-import") (part "C_CAP_0805"))
    )
    (comp (ref "C5_3")
      (value "C_CAP_0805")
      (footprint "eagle-import:C_0805")
      (libsource (lib "eagle-import") (part "C_CAP_0805"))
    )
    (comp (ref "C6_3")
      (value "0.22uF")
      (footprint "eagle-import:C_0805")
      (libsource (lib "eagle-import") (part "C_CAP_0805"))
    )
    (comp (ref "C7_3")
      (value "C_CAP_0805")
      (footprint "eagle-import:C_0805")
      (libsource (lib "eagle-import") (part "C_CAP_0805"))
    )
    (comp (ref "C8_3")
      (value "0.1uF")
      (footprint "eagle-import:C_0805")
      (libsource (lib "eagle-import") (part "C_CAP_0805"))
    )
    (comp (ref "C9_3")
      (value "C_CAP_0805")
      (footprint "eagle-import:C_0805")
      (libsource (lib "eagle-import") (part "C_CAP_0805"))
    )
    (comp (ref "C10_3")
      (value "C_CAP_0805")
      (footprint "eagle-import:C_0805")
      (libsource (lib "eagle-import") (part "C_CAP_0805"))
    )
    (comp (ref "C11_3")
      (value "C_CAP_0805")
      (footprint "eagle-import:C_0805")
      (libsource (lib "eagle-import") (part "C_CAP_0805"))
    )
    (comp (ref "C12_3")
      (value "C_CAP_0805")
      (footprint "eagle-import:C_0805")
      (libsource (lib "eagle-import") (part "C_CAP_0805"))
    )
    (comp (ref "E3")
      (value "J_MTA5P_100")
      (footprint "eagle-import:J_MTA100_5P")
      (libsource (lib "eagle-import") (part "J_MTA5P_100"))
    )
    (comp (ref "H3")
      (value "A3959")
      (footprint "eagle-import:DIP24")
      (libsource (lib "eagle-import") (part "Q_A3959"))
    )
    (comp (ref "JP4")
      (value "M025MM")
      (footprint "eagle-import:SCREWTERMINAL-5MM-2")
      (libsource (lib "eagle-import") (part "M025MM"))
    )
    (comp (ref "LED7")
      (value "LED1206")
      (footprint "eagle-import:LED-1206")
      (libsource (lib "eagle-import") (part "LED1206"))
    )
    (comp (ref "LED8")
      (value "LED1206")
      (footprint "eagle-import:LED-1206")
      (libsource (lib "eagle-import") (part "LED1206"))
    )
    (comp (ref "LED9")
      (value "LED1206")
      (footprint "eagle-import:LED-1206")
      (libsource (lib "eagle-import") (part "LED1206"))
    )
    (comp (ref "P3")
      (value "ATMEGA328P")
      (footprint "eagle-import:DIP28")
      (libsource (lib "eagle-import") (part "Q_ATMEGA328P"))
    )
    (comp (ref "R1_3")
      (value "200")
      (footprint "eagle-import:R_0805")
      (libsource (lib "eagle-import") (part "R_RES_0805"))
    )
    (comp (ref "R4_3")
      (value "51k")
      (footprint "eagle-import:R_0805")
      (libsource (lib "eagle-import") (part "R_RES_0805"))
    )
    (comp (ref "R5_3")
      (value "1k")
      (footprint "eagle-import:R_0805")
      (libsource (lib "eagle-import") (part "R_RES_0805"))
    )
    (comp (ref "R6_3")
      (value "10k")
      (footprint "eagle-import:R_0805")
      (libsource (lib "eagle-import") (part "R_RES_0805"))
    )
    (comp (ref "R7_3")
      (value "R_RES_2010")
      (footprint "eagle-import:R_2010")
      (libsource (lib "eagle-import") (part "R_RES_2010"))
    )
    (comp (ref "R8_3")
      (value "R_RES_0603")
      (footprint "eagle-import:R_0603")
      (libsource (lib "eagle-import") (part "R_RES_0603"))
    )
    (comp (ref "R9_3")
      (value "R_RES_0603")
      (footprint "eagle-import:R_0603")
      (libsource (lib "eagle-import") (part "R_RES_0603"))
    )
    (comp (ref "R15")
      (value "RESISTOR1206")
      (footprint "eagle-import:1206")
      (libsource (lib "eagle-import") (part "RESISTOR1206"))
    )
    (comp (ref "R16")
      (value "RESISTOR1206")
      (footprint "eagle-import:1206")
      (libsource (lib "eagle-import") (part "RESISTOR1206"))
    )
    (comp (ref "R17")
      (value "RESISTOR1206")
      (footprint "eagle-import:1206")
      (libsource (lib "eagle-import") (part "RESISTOR1206"))
    )
    (comp (ref "S3")
      (value "J_MC32857")
      (footprint "eagle-import:J_TOGGLE")
      (libsource (lib "eagle-import") (part "J_MC32857"))
    )
    (comp (ref "X3")
      (value "HC49S")
      (footprint "eagle-import:HC-49")
      (libsource (lib "eagle-import") (part "X_HC49SCRYSTAL"))
    )
  )
  (nets
    (net (code "1") (name "B1") (class "Default")
      (node (ref "JP9") (pin "2") (pinfunction "2_2") (pintype "passive"))
      (node (ref "MP") (pin "4") (pinfunction "PD2_4") (pintype "bidirectional"))
      (node (ref "R28") (pin "2") (pinfunction "2_2") (pintype "passive"))
    )
    (net (code "2") (name "B2") (class "Default")
      (node (ref "JP10") (pin "2") (pinfunction "2_2") (pintype "passive"))
      (node (ref "MP") (pin "5") (pinfunction "PD3_5") (pintype "bidirectional"))
      (node (ref "R29") (pin "2") (pinfunction "2_2") (pintype "passive"))
    )
    (net (code "3") (name "B3") (class "Default")
      (node (ref "JP11") (pin "2") (pinfunction "2_2") (pintype "passive"))
      (node (ref "MP") (pin "6") (pinfunction "PD4_6") (pintype "bidirectional"))
      (node (ref "R30") (pin "2") (pinfunction "2_2") (pintype "passive"))
    )
    (net (code "4") (name "B4") (class "Default")
      (node (ref "JP12") (pin "2") (pinfunction "2_2") (pintype "passive"))
      (node (ref "MP") (pin "13") (pinfunction "PD7_13") (pintype "bidirectional"))
      (node (ref "R31") (pin "2") (pinfunction "2_2") (pintype "passive"))
    )
    (net (code "5") (name "B5") (class "Default")
      (node (ref "JP13") (pin "2") (pinfunction "2_2") (pintype "passive"))
      (node (ref "MP") (pin "14") (pinfunction "PB0_14") (pintype "bidirectional"))
      (node (ref "R32") (pin "2") (pinfunction "2_2") (pintype "passive"))
    )
    (net (code "6") (name "BLANK1") (class "Default")
      (node (ref "H1") (pin "12") (pinfunction "BLANK_12") (pintype "bidirectional"))
      (node (ref "P1") (pin "17") (pinfunction "PB3_17") (pintype "bidirectional"))
    )
    (net (code "7") (name "BLANK2") (class "Default")
      (node (ref "H2") (pin "12") (pinfunction "BLANK_12") (pintype "bidirectional"))
      (node (ref "P2") (pin "17") (pinfunction "PB3_17") (pintype "bidirectional"))
    )
    (net (code "8") (name "BLANK3") (class "Default")
      (node (ref "H3") (pin "12") (pinfunction "BLANK_12") (pintype "bidirectional"))
      (node (ref "P3") (pin "17") (pinfunction "PB3_17") (pintype "bidirectional"))
    )
    (net (code "9") (name "BLANK4") (class "Default")
      (node (ref "H4") (pin "12") (pinfunction "BLANK_12") (pintype "bidirectional"))
      (node (ref "P4") (pin "17") (pinfunction "PB3_17") (pintype "bidirectional"))
    )
    (net (code "10") (name "BLANK5") (class "Default")
      (node (ref "H5") (pin "12") (pinfunction "BLANK_12") (pintype "bidirectional"))
      (node (ref "P5") (pin "17") (pinfunction "PB3_17") (pintype "bidirectional"))
    )
    (net (code "11") (name "D+") (class "Default")
      (node (ref "O6") (pin "3") (pinfunction "3_3") (pintype "passive"))
      (node (ref "R10") (pin "P$2") (pinfunction "2_P$2") (pintype "passive"))
      (node (ref "U$26") (pin "6") (pinfunction "A_6") (pintype "bidirectional"))
    )
    (net (code "12") (name "D-") (class "Default")
      (node (ref "O6") (pin "4") (pinfunction "4_4") (pintype "passive"))
      (node (ref "R10") (pin "P$1") (pinfunction "1_P$1") (pintype "passive"))
      (node (ref "U$26") (pin "7") (pinfunction "B_7") (pintype "bidirectional"))
    )
    (net (code "13") (name "D1") (class "Default")
      (node (ref "P1") (pin "3") (pinfunction "PD1_3") (pintype "bidirectional"))
    )
    (net (code "14") (name "D2") (class "Default")
      (node (ref "P2") (pin "3") (pinfunction "PD1_3") (pintype "bidirectional"))
    )
    (net (code "15") (name "D3") (class "Default")
      (node (ref "P3") (pin "3") (pinfunction "PD1_3") (pintype "bidirectional"))
    )
    (net (code "16") (name "D4") (class "Default")
      (node (ref "P4") (pin "3") (pinfunction "PD1_3") (pintype "bidirectional"))
    )
    (net (code "17") (name "D5") (class "Default")
      (node (ref "P5") (pin "3") (pinfunction "PD1_3") (pintype "bidirectional"))
    )
    (net (code "18") (name "D7") (class "Default")
      (node (ref "P6") (pin "3") (pinfunction "PD1_3") (pintype "bidirectional"))
    )
    (net (code "19") (name "DIR6") (class "Default")
      (node (ref "P6") (pin "6") (pinfunction "PD4_6") (pintype "bidirectional"))
      (node (ref "U$26") (pin "2") (pinfunction "RE_2") (pintype "bidirectional"))
      (node (ref "U$26") (pin "3") (pinfunction "DE_3") (pintype "bidirectional"))
    )
    (net (code "20") (name "DM") (class "Default")
      (node (ref "MD") (pin "2") (pinfunction "2_2") (pintype "passive"))
      (node (ref "MP") (pin "3") (pinfunction "PD1_3") (pintype "bidirectional"))
      (node (ref "Q3") (pin "3") (pinfunction "D_3") (pintype "bidirectional"))
    )
    (net (code "21") (name "EN1") (class "Default")
      (node (ref "H1") (pin "10") (pinfunction "EN_10") (pintype "bidirectional"))
      (node (ref "P1") (pin "19") (pinfunction "PB5_19") (pintype "bidirectional"))
    )
    (net (code "22") (name "EN2") (class "Default")
      (node (ref "H2") (pin "10") (pinfunction "EN_10") (pintype "bidirectional"))
      (node (ref "P2") (pin "19") (pinfunction "PB5_19") (pintype "bidirectional"))
    )
    (net (code "23") (name "EN3") (class "Default")
      (node (ref "H3") (pin "10") (pinfunction "EN_10") (pintype "bidirectional"))
      (node (ref "P3") (pin "19") (pinfunction "PB5_19") (pintype "bidirectional"))
    )
    (net (code "24") (name "EN4") (class "Default")
      (node (ref "H4") (pin "10") (pinfunction "EN_10") (pintype "bidirectional"))
      (node (ref "P4") (pin "19") (pinfunction "PB5_19") (pintype "bidirectional"))
    )
    (net (code "25") (name "EN5") (class "Default")
      (node (ref "H5") (pin "10") (pinfunction "EN_10") (pintype "bidirectional"))
      (node (ref "P5") (pin "19") (pinfunction "PB5_19") (pintype "bidirectional"))
    )
    (net (code "26") (name "EXTMODE1") (class "Default")
      (node (ref "H1") (pin "15") (pinfunction "EXTMODE_15") (pintype "bidirectional"))
      (node (ref "P1") (pin "16") (pinfunction "PB2_16") (pintype "bidirectional"))
    )
    (net (code "27") (name "EXTMODE2") (class "Default")
      (node (ref "H2") (pin "15") (pinfunction "EXTMODE_15") (pintype "bidirectional"))
      (node (ref "P2") (pin "16") (pinfunction "PB2_16") (pintype "bidirectional"))
    )
    (net (code "28") (name "EXTMODE3") (class "Default")
      (node (ref "H3") (pin "15") (pinfunction "EXTMODE_15") (pintype "bidirectional"))
      (node (ref "P3") (pin "16") (pinfunction "PB2_16") (pintype "bidirectional"))
    )
    (net (code "29") (name "EXTMODE4") (class "Default")
      (node (ref "H4") (pin "15") (pinfunction "EXTMODE_15") (pintype "bidirectional"))
      (node (ref "P4") (pin "16") (pinfunction "PB2_16") (pintype "bidirectional"))
    )
    (net (code "30") (name "EXTMODE5") (class "Default")
      (node (ref "H5") (pin "15") (pinfunction "EXTMODE_15") (pintype "bidirectional"))
      (node (ref "P5") (pin "16") (pinfunction "PB2_16") (pintype "bidirectional"))
    )
    (net (code "31") (name "GND") (class "Default")
      (node (ref "C10") (pin "2") (pinfunction "2_2") (pintype "passive"))
      (node (ref "C10_1") (pin "1") (pinfunction "1_1") (pintype "passive"))
      (node (ref "C10_2") (pin "1") (pinfunction "1_1") (pintype "passive"))
      (node (ref "C10_3") (pin "1") (pinfunction "1_1") (pintype "passive"))
      (node (ref "C10_4") (pin "1") (pinfunction "1_1") (pintype "passive"))
      (node (ref "C10_5") (pin "1") (pinfunction "1_1") (pintype "passive"))
      (node (ref "C11_1") (pin "2") (pinfunction "2_2") (pintype "passive"))
      (node (ref "C11_2") (pin "2") (pinfunction "2_2") (pintype "passive"))
      (node (ref "C11_3") (pin "2") (pinfunction "2_2") (pintype "passive"))
      (node (ref "C11_4") (pin "2") (pinfunction "2_2") (pintype "passive"))
      (node (ref "C11_5") (pin "2") (pinfunction "2_2") (pintype "passive"))
      (node (ref "C12_1") (pin "1") (pinfunction "1_1") (pintype "passive"))
      (node (ref "C12_2") (pin "1") (pinfunction "1_1") (pintype "passive"))
      (node (ref "C12_3") (pin "1") (pinfunction "1_1") (pintype "passive"))
      (node (ref "C12_4") (pin "1") (pinfunction "1_1") (pintype "passive"))
      (node (ref "C12_5") (pin "1") (pinfunction "1_1") (pintype "passive"))
      (node (ref "C1_1") (pin "1") (pinfunction "1_1") (pintype "passive"))
      (node (ref "C1_2") (pin "1") (pinfunction "1_1") (pintype "passive"))
      (node (ref "C1_3") (pin "1") (pinfunction "1_1") (pintype "passive"))
      (node (ref "C1_4") (pin "1") (pinfunction "1_1") (pintype "passive"))
      (node (ref "C1_5") (pin "1") (pinfunction "1_1") (pintype "passive"))
      (node (ref "C1_6") (pin "1") (pinfunction "1_1") (pintype "passive"))
      (node (ref "C1_M") (pin "1") (pinfunction "1_1") (pintype "passive"))
      (node (ref "C2_1") (pin "1") (pinfunction "1_1") (pintype "passive"))
      (node (ref "C2_2") (pin "1") (pinfunction "1_1") (pintype "passive"))
      (node (ref "C2_3") (pin "1") (pinfunction "1_1") (pintype "passive"))
      (node (ref "C2_4") (pin "1") (pinfunction "1_1") (pintype "passive"))
      (node (ref "C2_5") (pin "1") (pinfunction "1_1") (pintype "passive"))
      (node (ref "C2_6") (pin "1") (pinfunction "1_1") (pintype "passive"))
      (node (ref "C2_M") (pin "1") (pinfunction "1_1") (pintype "passive"))
      (node (ref "C3_1") (pin "1") (pinfunction "1_1") (pintype "passive"))
      (node (ref "C3_2") (pin "1") (pinfunction "1_1") (pintype "passive"))
      (node (ref "C3_3") (pin "1") (pinfunction "1_1") (pintype "passive"))
      (node (ref "C3_4") (pin "1") (pinfunction "1_1") (pintype "passive"))
      (node (ref "C3_5") (pin "1") (pinfunction "1_1") (pintype "passive"))
      (node (ref "C3_6") (pin "1") (pinfunction "1_1") (pintype "passive"))
      (node (ref "C3_M") (pin "1") (pinfunction "1_1") (pintype "passive"))
      (node (ref "C4_1") (pin "2") (pinfunction "2_2") (pintype "passive"))
      (node (ref "C4_2") (pin "2") (pinfunction "2_2") (pintype "passive"))
      (node (ref "C4_3") (pin "2") (pinfunction "2_2") (pintype "passive"))
      (node (ref "C4_4") (pin "2") (pinfunction "2_2") (pintype "passive"))
      (node (ref "C4_5") (pin "2") (pinfunction "2_2") (pintype "passive"))
      (node (ref "C4_6") (pin "2") (pinfunction "2_2") (pintype "passive"))
      (node (ref "C4_M") (pin "2") (pinfunction "2_2") (pintype "passive"))
      (node (ref "C5_1") (pin "2") (pinfunction "2_2") (pintype "passive"))
      (node (ref "C5_2") (pin "2") (pinfunction "2_2") (pintype "passive"))
      (node (ref "C5_3") (pin "2") (pinfunction "2_2") (pintype "passive"))
      (node (ref "C5_4") (pin "2") (pinfunction "2_2") (pintype "passive"))
      (node (ref "C5_5") (pin "2") (pinfunction "2_2") (pintype "passive"))
      (node (ref "C5_6") (pin "2") (pinfunction "2_2") (pintype "passive"))
      (node (ref "C5_M") (pin "2") (pinfunction "2_2") (pintype "passive"))
      (node (ref "C7_1") (pin "2") (pinfunction "2_2") (pintype "passive"))
      (node (ref "C7_2") (pin "2") (pinfunction "2_2") (pintype "passive"))
      (node (ref "C7_3") (pin "2") (pinfunction "2_2") (pintype "passive"))
      (node (ref "C7_4") (pin "2") (pinfunction "2_2") (pintype "passive"))
      (node (ref "C7_5") (pin "2") (pinfunction "2_2") (pintype "passive"))
      (node (ref "C8_1") (pin "2") (pinfunction "2_2") (pintype "passive"))
      (node (ref "C8_2") (pin "2") (pinfunction "2_2") (pintype "passive"))
      (node (ref "C8_3") (pin "2") (pinfunction "2_2") (pintype "passive"))
      (node (ref "C8_4") (pin "2") (pinfunction "2_2") (pintype "passive"))
      (node (ref "C8_5") (pin "2") (pinfunction "2_2") (pintype "passive"))
      (node (ref "C9_1") (pin "2") (pinfunction "2_2") (pintype "passive"))
      (node (ref "C9_2") (pin "2") (pinfunction "2_2") (pintype "passive"))
      (node (ref "C9_3") (pin "2") (pinfunction "2_2") (pintype "passive"))
      (node (ref "C9_4") (pin "2") (pinfunction "2_2") (pintype "passive"))
      (node (ref "C9_5") (pin "2") (pinfunction "2_2") (pintype "passive"))
      (node (ref "CV3") (pin "2") (pinfunction "2_2") (pintype "passive"))
      (node (ref "CV4") (pin "2") (pinfunction "2_2") (pintype "passive"))
      (node (ref "E1") (pin "5") (pinfunction "5_5") (pintype "passive"))
      (node (ref "E2") (pin "5") (pinfunction "5_5") (pintype "passive"))
      (node (ref "E3") (pin "5") (pinfunction "5_5") (pintype "passive"))
      (node (ref "E4") (pin "5") (pinfunction "5_5") (pintype "passive"))
      (node (ref "E5") (pin "5") (pinfunction "5_5") (pintype "passive"))
      (node (ref "H1") (pin "18") (pinfunction "GND4_18") (pintype "bidirectional"))
      (node (ref "H1") (pin "19") (pinfunction "GND5_19") (pintype "bidirectional"))
      (node (ref "H1") (pin "5") (pinfunction "GND_5") (pintype "bidirectional"))
      (node (ref "H1") (pin "6") (pinfunction "GND1_6") (pintype "bidirectional"))
      (node (ref "H1") (pin "7") (pinfunction "GND2_7") (pintype "bidirectional"))
      (node (ref "H1") (pin "8") (pinfunction "GND3_8") (pintype "bidirectional"))
      (node (ref "H2") (pin "18") (pinfunction "GND4_18") (pintype "bidirectional"))
      (node (ref "H2") (pin "19") (pinfunction "GND5_19") (pintype "bidirectional"))
      (node (ref "H2") (pin "5") (pinfunction "GND_5") (pintype "bidirectional"))
      (node (ref "H2") (pin "6") (pinfunction "GND1_6") (pintype "bidirectional"))
      (node (ref "H2") (pin "7") (pinfunction "GND2_7") (pintype "bidirectional"))
      (node (ref "H2") (pin "8") (pinfunction "GND3_8") (pintype "bidirectional"))
      (node (ref "H3") (pin "18") (pinfunction "GND4_18") (pintype "bidirectional"))
      (node (ref "H3") (pin "19") (pinfunction "GND5_19") (pintype "bidirectional"))
      (node (ref "H3") (pin "5") (pinfunction "GND_5") (pintype "bidirectional"))
      (node (ref "H3") (pin "6") (pinfunction "GND1_6") (pintype "bidirectional"))
      (node (ref "H3") (pin "7") (pinfunction "GND2_7") (pintype "bidirectional"))
      (node (ref "H3") (pin "8") (pinfunction "GND3_8") (pintype "bidirectional"))
      (node (ref "H4") (pin "18") (pinfunction "GND4_18") (pintype "bidirectional"))
      (node (ref "H4") (pin "19") (pinfunction "GND5_19") (pintype "bidirectional"))
      (node (ref "H4") (pin "5") (pinfunction "GND_5") (pintype "bidirectional"))
      (node (ref "H4") (pin "6") (pinfunction "GND1_6") (pintype "bidirectional"))
      (node (ref "H4") (pin "7") (pinfunction "GND2_7") (pintype "bidirectional"))
      (node (ref "H4") (pin "8") (pinfunction "GND3_8") (pintype "bidirectional"))
      (node (ref "H5") (pin "18") (pinfunction "GND4_18") (pintype "bidirectional"))
      (node (ref "H5") (pin "19") (pinfunction "GND5_19") (pintype "bidirectional"))
      (node (ref "H5") (pin "5") (pinfunction "GND_5") (pintype "bidirectional"))
      (node (ref "H5") (pin "6") (pinfunction "GND1_6") (pintype "bidirectional"))
      (node (ref "H5") (pin "7") (pinfunction "GND2_7") (pintype "bidirectional"))
      (node (ref "H5") (pin "8") (pinfunction "GND3_8") (pintype "bidirectional"))
      (node (ref "J6") (pin "P$1") (pinfunction "1_P$1") (pintype "bidirectional"))
      (node (ref "JP1") (pin "2") (pinfunction "2_2") (pintype "passive"))
      (node (ref "JP14") (pin "1") (pinfunction "1_1") (pintype "passive"))
      (node (ref "JP15") (pin "1") (pinfunction "1_1") (pintype "passive"))
      (node (ref "LED1") (pin "C") (pinfunction "C_C") (pintype "passive"))
      (node (ref "LED10") (pin "C") (pinfunction "C_C") (pintype "passive"))
      (node (ref "LED11") (pin "C") (pinfunction "C_C") (pintype "passive"))
      (node (ref "LED12") (pin "C") (pinfunction "C_C") (pintype "passive"))
      (node (ref "LED13") (pin "C") (pinfunction "C_C") (pintype "passive"))
      (node (ref "LED14") (pin "C") (pinfunction "C_C") (pintype "passive"))
      (node (ref "LED15") (pin "C") (pinfunction "C_C") (pintype "passive"))
      (node (ref "LED16") (pin "C") (pinfunction "C_C") (pintype "passive"))
      (node (ref "LED17") (pin "C") (pinfunction "C_C") (pintype "passive"))
      (node (ref "LED18") (pin "C") (pinfunction "C_C") (pintype "passive"))
      (node (ref "LED2") (pin "C") (pinfunction "C_C") (pintype "passive"))
      (node (ref "LED21") (pin "C") (pinfunction "C_C") (pintype "passive"))
      (node (ref "LED3") (pin "C") (pinfunction "C_C") (pintype "passive"))
      (node (ref "LED4") (pin "C") (pinfunction "C_C") (pintype "passive"))
      (node (ref "LED5") (pin "C") (pinfunction "C_C") (pintype "passive"))
      (node (ref "LED6") (pin "C") (pinfunction "C_C") (pintype "passive"))
      (node (ref "LED7") (pin "C") (pinfunction "C_C") (pintype "passive"))
      (node (ref "LED8") (pin "C") (pinfunction "C_C") (pintype "passive"))
      (node (ref "LED9") (pin "C") (pinfunction "C_C") (pintype "passive"))
      (node (ref "MD") (pin "1") (pinfunction "1_1") (pintype "passive"))
      (node (ref "MP") (pin "22") (pinfunction "GND1_22") (pintype "bidirectional"))
      (node (ref "MP") (pin "8") (pinfunction "GND_8") (pintype "bidirectional"))
      (node (ref "MS") (pin "P$1") (pinfunction "1_P$1") (pintype "bidirectional"))
      (node (ref "MS1") (pin "P$1") (pinfunction "1_P$1") (pintype "bidirectional"))
      (node (ref "O6") (pin "1") (pinfunction "1_1") (pintype "passive"))
      (node (ref "P1") (pin "22") (pinfunction "GND1_22") (pintype "bidirectional"))
      (node (ref "P1") (pin "8") (pinfunction "GND_8") (pintype "bidirectional"))
      (node (ref "P2") (pin "22") (pinfunction "GND1_22") (pintype "bidirectional"))
      (node (ref "P2") (pin "8") (pinfunction "GND_8") (pintype "bidirectional"))
      (node (ref "P3") (pin "22") (pinfunction "GND1_22") (pintype "bidirectional"))
      (node (ref "P3") (pin "8") (pinfunction "GND_8") (pintype "bidirectional"))
      (node (ref "P4") (pin "22") (pinfunction "GND1_22") (pintype "bidirectional"))
      (node (ref "P4") (pin "8") (pinfunction "GND_8") (pintype "bidirectional"))
      (node (ref "P5") (pin "22") (pinfunction "GND1_22") (pintype "bidirectional"))
      (node (ref "P5") (pin "8") (pinfunction "GND_8") (pintype "bidirectional"))
      (node (ref "P6") (pin "22") (pinfunction "GND1_22") (pintype "bidirectional"))
      (node (ref "P6") (pin "8") (pinfunction "GND_8") (pintype "bidirectional"))
      (node (ref "Q1") (pin "3") (pinfunction "S_3") (pintype "passive"))
      (node (ref "Q2") (pin "3") (pinfunction "S_3") (pintype "passive"))
      (node (ref "Q3") (pin "4") (pinfunction "GND_4") (pintype "bidirectional"))
      (node (ref "Q4") (pin "3") (pinfunction "S_3") (pintype "passive"))
      (node (ref "Q5") (pin "2") (pinfunction "GND_2") (pintype "bidirectional"))
      (node (ref "R28") (pin "1") (pinfunction "1_1") (pintype "passive"))
      (node (ref "R29") (pin "1") (pinfunction "1_1") (pintype "passive"))
      (node (ref "R3") (pin "P$1") (pinfunction "1_P$1") (pintype "passive"))
      (node (ref "R30") (pin "1") (pinfunction "1_1") (pintype "passive"))
      (node (ref "R31") (pin "1") (pinfunction "1_1") (pintype "passive"))
      (node (ref "R32") (pin "1") (pinfunction "1_1") (pintype "passive"))
      (node (ref "R6") (pin "P$1") (pinfunction "1_P$1") (pintype "passive"))
      (node (ref "R6_1") (pin "2") (pinfunction "2_2") (pintype "passive"))
      (node (ref "R6_2") (pin "2") (pinfunction "2_2") (pintype "passive"))
      (node (ref "R6_3") (pin "2") (pinfunction "2_2") (pintype "passive"))
      (node (ref "R6_4") (pin "2") (pinfunction "2_2") (pintype "passive"))
      (node (ref "R6_5") (pin "2") (pinfunction "2_2") (pintype "passive"))
      (node (ref "R7") (pin "P$1") (pinfunction "1_P$1") (pintype "passive"))
      (node (ref "R7_1") (pin "2") (pinfunction "2_2") (pintype "passive"))
      (node (ref "R7_2") (pin "2") (pinfunction "2_2") (pintype "passive"))
      (node (ref "R7_3") (pin "2") (pinfunction "2_2") (pintype "passive"))
      (node (ref "R7_4") (pin "2") (pinfunction "2_2") (pintype "passive"))
      (node (ref "R7_5") (pin "2") (pinfunction "2_2") (pintype "passive"))
      (node (ref "S1") (pin "P$1") (pinfunction "1_P$1") (pintype "bidirectional"))
      (node (ref "S2") (pin "P$1") (pinfunction "1_P$1") (pintype "bidirectional"))
      (node (ref "S3") (pin "P$1") (pinfunction "1_P$1") (pintype "bidirectional"))
      (node (ref "S4") (pin "P$1") (pinfunction "1_P$1") (pintype "bidirectional"))
      (node (ref "S5") (pin "P$1") (pinfunction "1_P$1") (pintype "bidirectional"))
      (node (ref "SJ1") (pin "1") (pinfunction "1_1") (pintype "passive"))
      (node (ref "U$26") (pin "5") (pinfunction "GND_5") (pintype "bidirectional"))
    )
    (net (code "32") (name "INTERRUPT1_1") (class "Default")
      (node (ref "E1") (pin "2") (pinfunction "2_2") (pintype "passive"))
      (node (ref "P1") (pin "5") (pinfunction "PD3_5") (pintype "bidirectional"))
      (node (ref "R9_1") (pin "1") (pinfunction "1_1") (pintype "passive"))
    )
    (net (code "33") (name "INTERRUPT1_2") (class "Default")
      (node (ref "E2") (pin "2") (pinfunction "2_2") (pintype "passive"))
      (node (ref "P2") (pin "5") (pinfunction "PD3_5") (pintype "bidirectional"))
      (node (ref "R9_2") (pin "1") (pinfunction "1_1") (pintype "passive"))
    )
    (net (code "34") (name "INTERRUPT1_3") (class "Default")
      (node (ref "E3") (pin "2") (pinfunction "2_2") (pintype "passive"))
      (node (ref "P3") (pin "5") (pinfunction "PD3_5") (pintype "bidirectional"))
      (node (ref "R9_3") (pin "1") (pinfunction "1_1") (pintype "passive"))
    )
    (net (code "35") (name "INTERRUPT1_4") (class "Default")
      (node (ref "E4") (pin "2") (pinfunction "2_2") (pintype "passive"))
      (node (ref "P4") (pin "5") (pinfunction "PD3_5") (pintype "bidirectional"))
      (node (ref "R9_4") (pin "1") (pinfunction "1_1") (pintype "passive"))
    )
    (net (code "36") (name "INTERRUPT1_5") (class "Default")
      (node (ref "E5") (pin "2") (pinfunction "2_2") (pintype "passive"))
      (node (ref "P5") (pin "5") (pinfunction "PD3_5") (pintype "bidirectional"))
      (node (ref "R9_5") (pin "1") (pinfunction "1_1") (pintype "passive"))
    )
    (net (code "37") (name "INTERRUPT2_1") (class "Default")
      (node (ref "E1") (pin "1") (pinfunction "1_1") (pintype "passive"))
      (node (ref "P1") (pin "4") (pinfunction "PD2_4") (pintype "bidirectional"))
    )
    (net (code "38") (name "INTERRUPT2_2") (class "Default")
      (node (ref "E2") (pin "1") (pinfunction "1_1") (pintype "passive"))
      (node (ref "P2") (pin "4") (pinfunction "PD2_4") (pintype "bidirectional"))
    )
    (net (code "39") (name "INTERRUPT2_3") (class "Default")
      (node (ref "E3") (pin "1") (pinfunction "1_1") (pintype "passive"))
      (node (ref "P3") (pin "4") (pinfunction "PD2_4") (pintype "bidirectional"))
    )
    (net (code "40") (name "INTERRUPT2_4") (class "Default")
      (node (ref "E4") (pin "1") (pinfunction "1_1") (pintype "passive"))
      (node (ref "P4") (pin "4") (pinfunction "PD2_4") (pintype "bidirectional"))
    )
    (net (code "41") (name "INTERRUPT2_5") (class "Default")
      (node (ref "E5") (pin "1") (pinfunction "1_1") (pintype "passive"))
      (node (ref "P5") (pin "4") (pinfunction "PD2_4") (pintype "bidirectional"))
    )
    (net (code "42") (name "ISENSE1") (class "Default")
      (node (ref "C9_1") (pin "1") (pinfunction "1_1") (pintype "passive"))
      (node (ref "H1") (pin "17") (pinfunction "SENSE_17") (pintype "bidirectional"))
      (node (ref "P1") (pin "26") (pinfunction "PC3_26") (pintype "bidirectional"))
      (node (ref "R7_1") (pin "1") (pinfunction "1_1") (pintype "passive"))
    )
    (net (code "43") (name "ISENSE2") (class "Default")
      (node (ref "C9_2") (pin "1") (pinfunction "1_1") (pintype "passive"))
      (node (ref "H2") (pin "17") (pinfunction "SENSE_17") (pintype "bidirectional"))
      (node (ref "P2") (pin "26") (pinfunction "PC3_26") (pintype "bidirectional"))
      (node (ref "R7_2") (pin "1") (pinfunction "1_1") (pintype "passive"))
    )
    (net (code "44") (name "ISENSE3") (class "Default")
      (node (ref "C9_3") (pin "1") (pinfunction "1_1") (pintype "passive"))
      (node (ref "H3") (pin "17") (pinfunction "SENSE_17") (pintype "bidirectional"))
      (node (ref "P3") (pin "26") (pinfunction "PC3_26") (pintype "bidirectional"))
      (node (ref "R7_3") (pin "1") (pinfunction "1_1") (pintype "passive"))
    )
    (net (code "45") (name "ISENSE4") (class "Default")
      (node (ref "C9_4") (pin "1") (pinfunction "1_1") (pintype "passive"))
      (node (ref "H4") (pin "17") (pinfunction "SENSE_17") (pintype "bidirectional"))
      (node (ref "P4") (pin "26") (pinfunction "PC3_26") (pintype "bidirectional"))
      (node (ref "R7_4") (pin "1") (pinfunction "1_1") (pintype "passive"))
    )
    (net (code "46") (name "ISENSE5") (class "Default")
      (node (ref "C9_5") (pin "1") (pinfunction "1_1") (pintype "passive"))
      (node (ref "H5") (pin "17") (pinfunction "SENSE_17") (pintype "bidirectional"))
      (node (ref "P5") (pin "26") (pinfunction "PC3_26") (pintype "bidirectional"))
      (node (ref "R7_5") (pin "1") (pinfunction "1_1") (pintype "passive"))
    )
    (net (code "47") (name "LED1_1") (class "Default")
      (node (ref "P1") (pin "12") (pinfunction "PD6_12") (pintype "bidirectional"))
      (node (ref "R8") (pin "2") (pinfunction "2_2") (pintype "passive"))
    )
    (net (code "48") (name "LED1_2") (class "Default")
      (node (ref "P2") (pin "12") (pinfunction "PD6_12") (pintype "bidirectional"))
      (node (ref "R12") (pin "2") (pinfunction "2_2") (pintype "passive"))
    )
    (net (code "49") (name "LED1_3") (class "Default")
      (node (ref "P3") (pin "12") (pinfunction "PD6_12") (pintype "bidirectional"))
      (node (ref "R15") (pin "2") (pinfunction "2_2") (pintype "passive"))
    )
    (net (code "50") (name "LED1_4") (class "Default")
      (node (ref "P4") (pin "12") (pinfunction "PD6_12") (pintype "bidirectional"))
      (node (ref "R18") (pin "2") (pinfunction "2_2") (pintype "passive"))
    )
    (net (code "51") (name "LED1_5") (class "Default")
      (node (ref "P5") (pin "12") (pinfunction "PD6_12") (pintype "bidirectional"))
      (node (ref "R21") (pin "2") (pinfunction "2_2") (pintype "passive"))
    )
    (net (code "52") (name "LED1_6") (class "Default")
      (node (ref "P6") (pin "12") (pinfunction "PD6_12") (pintype "bidirectional"))
      (node (ref "R24") (pin "2") (pinfunction "2_2") (pintype "passive"))
    )
    (net (code "53") (name "LED2_1") (class "Default")
      (node (ref "P1") (pin "13") (pinfunction "PD7_13") (pintype "bidirectional"))
      (node (ref "R9") (pin "2") (pinfunction "2_2") (pintype "passive"))
    )
    (net (code "54") (name "LED2_2") (class "Default")
      (node (ref "P2") (pin "13") (pinfunction "PD7_13") (pintype "bidirectional"))
      (node (ref "R13") (pin "2") (pinfunction "2_2") (pintype "passive"))
    )
    (net (code "55") (name "LED2_3") (class "Default")
      (node (ref "P3") (pin "13") (pinfunction "PD7_13") (pintype "bidirectional"))
      (node (ref "R16") (pin "2") (pinfunction "2_2") (pintype "passive"))
    )
    (net (code "56") (name "LED2_4") (class "Default")
      (node (ref "P4") (pin "13") (pinfunction "PD7_13") (pintype "bidirectional"))
      (node (ref "R19") (pin "2") (pinfunction "2_2") (pintype "passive"))
    )
    (net (code "57") (name "LED2_5") (class "Default")
      (node (ref "P5") (pin "13") (pinfunction "PD7_13") (pintype "bidirectional"))
      (node (ref "R22") (pin "2") (pinfunction "2_2") (pintype "passive"))
    )
    (net (code "58") (name "LED2_6") (class "Default")
      (node (ref "P6") (pin "13") (pinfunction "PD7_13") (pintype "bidirectional"))
      (node (ref "R25") (pin "2") (pinfunction "2_2") (pintype "passive"))
    )
    (net (code "59") (name "N$15") (class "Default")
      (node (ref "P1") (pin "1") (pinfunction "PC6_1") (pintype "bidirectional"))
      (node (ref "R11") (pin "2") (pinfunction "2_2") (pintype "passive"))
      (node (ref "R1_1") (pin "1") (pinfunction "1_1") (pintype "passive"))
      (node (ref "S1") (pin "P$2") (pinfunction "2_P$2") (pintype "bidirectional"))
    )
    (net (code "60") (name "N$30") (class "Default")
      (node (ref "P2") (pin "1") (pinfunction "PC6_1") (pintype "bidirectional"))
      (node (ref "R14") (pin "2") (pinfunction "2_2") (pintype "passive"))
      (node (ref "R1_2") (pin "1") (pinfunction "1_1") (pintype "passive"))
      (node (ref "S2") (pin "P$2") (pinfunction "2_P$2") (pintype "bidirectional"))
    )
    (net (code "61") (name "N$43") (class "Default")
      (node (ref "P3") (pin "1") (pinfunction "PC6_1") (pintype "bidirectional"))
      (node (ref "R17") (pin "2") (pinfunction "2_2") (pintype "passive"))
      (node (ref "R1_3") (pin "1") (pinfunction "1_1") (pintype "passive"))
      (node (ref "S3") (pin "P$2") (pinfunction "2_P$2") (pintype "bidirectional"))
    )
    (net (code "62") (name "N$56") (class "Default")
      (node (ref "P4") (pin "1") (pinfunction "PC6_1") (pintype "bidirectional"))
      (node (ref "R1_4") (pin "1") (pinfunction "1_1") (pintype "passive"))
      (node (ref "R20") (pin "2") (pinfunction "2_2") (pintype "passive"))
      (node (ref "S4") (pin "P$2") (pinfunction "2_P$2") (pintype "bidirectional"))
    )
    (net (code "63") (name "N$69") (class "Default")
      (node (ref "P5") (pin "1") (pinfunction "PC6_1") (pintype "bidirectional"))
      (node (ref "R1_5") (pin "1") (pinfunction "1_1") (pintype "passive"))
      (node (ref "R23") (pin "2") (pinfunction "2_2") (pintype "passive"))
      (node (ref "S5") (pin "P$2") (pinfunction "2_P$2") (pintype "bidirectional"))
    )
    (net (code "64") (name "N$88") (class "Default")
      (node (ref "MP") (pin "1") (pinfunction "PC6_1") (pintype "bidirectional"))
      (node (ref "MS") (pin "P$2") (pinfunction "2_P$2") (pintype "bidirectional"))
      (node (ref "R1_M") (pin "1") (pinfunction "1_1") (pintype "passive"))
      (node (ref "R27") (pin "2") (pinfunction "2_2") (pintype "passive"))
    )
    (net (code "65") (name "Net-(E1-Pad3)") (class "Default")
      (node (ref "E1") (pin "3") (pinfunction "3_3") (pintype "passive"))
      (node (ref "R8_1") (pin "1") (pinfunction "1_1") (pintype "passive"))
    )
    (net (code "66") (name "Net-(E2-Pad3)") (class "Default")
      (node (ref "E2") (pin "3") (pinfunction "3_3") (pintype "passive"))
      (node (ref "R8_2") (pin "1") (pinfunction "1_1") (pintype "passive"))
    )
    (net (code "67") (name "Net-(E3-Pad3)") (class "Default")
      (node (ref "E3") (pin "3") (pinfunction "3_3") (pintype "passive"))
      (node (ref "R8_3") (pin "1") (pinfunction "1_1") (pintype "passive"))
    )
    (net (code "68") (name "Net-(E4-Pad3)") (class "Default")
      (node (ref "E4") (pin "3") (pinfunction "3_3") (pintype "passive"))
      (node (ref "R8_4") (pin "1") (pinfunction "1_1") (pintype "passive"))
    )
    (net (code "69") (name "Net-(E5-Pad3)") (class "Default")
      (node (ref "E5") (pin "3") (pinfunction "3_3") (pintype "passive"))
      (node (ref "R8_5") (pin "1") (pinfunction "1_1") (pintype "passive"))
    )
    (net (code "70") (name "Net-(H1-CP)") (class "Default")
      (node (ref "C12_1") (pin "2") (pinfunction "2_2") (pintype "passive"))
      (node (ref "H1") (pin "24") (pinfunction "CP_24") (pintype "bidirectional"))
    )
    (net (code "71") (name "Net-(H1-CP1)") (class "Default")
      (node (ref "C6_1") (pin "2") (pinfunction "2_2") (pintype "passive"))
      (node (ref "H1") (pin "2") (pinfunction "CP1_2") (pintype "bidirectional"))
    )
    (net (code "72") (name "Net-(H1-CP2)") (class "Default")
      (node (ref "C6_1") (pin "1") (pinfunction "1_1") (pintype "passive"))
      (node (ref "H1") (pin "1") (pinfunction "CP2_1") (pintype "bidirectional"))
    )
    (net (code "73") (name "Net-(H1-REF)") (class "Default")
      (node (ref "C8_1") (pin "1") (pinfunction "1_1") (pintype "passive"))
      (node (ref "H1") (pin "14") (pinfunction "REF_14") (pintype "bidirectional"))
      (node (ref "R5_1") (pin "1") (pinfunction "1_1") (pintype "passive"))
      (node (ref "R6_1") (pin "1") (pinfunction "1_1") (pintype "passive"))
    )
    (net (code "74") (name "Net-(H1-ROSC)") (class "Default")
      (node (ref "H1") (pin "4") (pinfunction "ROSC_4") (pintype "bidirectional"))
      (node (ref "R4_1") (pin "2") (pinfunction "2_2") (pintype "passive"))
    )
    (net (code "75") (name "Net-(H1-VREG)") (class "Default")
      (node (ref "C11_1") (pin "1") (pinfunction "1_1") (pintype "passive"))
      (node (ref "H1") (pin "23") (pinfunction "VREG_23") (pintype "bidirectional"))
    )
    (net (code "76") (name "Net-(H2-CP)") (class "Default")
      (node (ref "C12_2") (pin "2") (pinfunction "2_2") (pintype "passive"))
      (node (ref "H2") (pin "24") (pinfunction "CP_24") (pintype "bidirectional"))
    )
    (net (code "77") (name "Net-(H2-CP1)") (class "Default")
      (node (ref "C6_2") (pin "2") (pinfunction "2_2") (pintype "passive"))
      (node (ref "H2") (pin "2") (pinfunction "CP1_2") (pintype "bidirectional"))
    )
    (net (code "78") (name "Net-(H2-CP2)") (class "Default")
      (node (ref "C6_2") (pin "1") (pinfunction "1_1") (pintype "passive"))
      (node (ref "H2") (pin "1") (pinfunction "CP2_1") (pintype "bidirectional"))
    )
    (net (code "79") (name "Net-(H2-REF)") (class "Default")
      (node (ref "C8_2") (pin "1") (pinfunction "1_1") (pintype "passive"))
      (node (ref "H2") (pin "14") (pinfunction "REF_14") (pintype "bidirectional"))
      (node (ref "R5_2") (pin "1") (pinfunction "1_1") (pintype "passive"))
      (node (ref "R6_2") (pin "1") (pinfunction "1_1") (pintype "passive"))
    )
    (net (code "80") (name "Net-(H2-ROSC)") (class "Default")
      (node (ref "H2") (pin "4") (pinfunction "ROSC_4") (pintype "bidirectional"))
      (node (ref "R4_2") (pin "2") (pinfunction "2_2") (pintype "passive"))
    )
    (net (code "81") (name "Net-(H2-VREG)") (class "Default")
      (node (ref "C11_2") (pin "1") (pinfunction "1_1") (pintype "passive"))
      (node (ref "H2") (pin "23") (pinfunction "VREG_23") (pintype "bidirectional"))
    )
    (net (code "82") (name "Net-(H3-CP)") (class "Default")
      (node (ref "C12_3") (pin "2") (pinfunction "2_2") (pintype "passive"))
      (node (ref "H3") (pin "24") (pinfunction "CP_24") (pintype "bidirectional"))
    )
    (net (code "83") (name "Net-(H3-CP1)") (class "Default")
      (node (ref "C6_3") (pin "2") (pinfunction "2_2") (pintype "passive"))
      (node (ref "H3") (pin "2") (pinfunction "CP1_2") (pintype "bidirectional"))
    )
    (net (code "84") (name "Net-(H3-CP2)") (class "Default")
      (node (ref "C6_3") (pin "1") (pinfunction "1_1") (pintype "passive"))
      (node (ref "H3") (pin "1") (pinfunction "CP2_1") (pintype "bidirectional"))
    )
    (net (code "85") (name "Net-(H3-REF)") (class "Default")
      (node (ref "C8_3") (pin "1") (pinfunction "1_1") (pintype "passive"))
      (node (ref "H3") (pin "14") (pinfunction "REF_14") (pintype "bidirectional"))
      (node (ref "R5_3") (pin "1") (pinfunction "1_1") (pintype "passive"))
      (node (ref "R6_3") (pin "1") (pinfunction "1_1") (pintype "passive"))
    )
    (net (code "86") (name "Net-(H3-ROSC)") (class "Default")
      (node (ref "H3") (pin "4") (pinfunction "ROSC_4") (pintype "bidirectional"))
      (node (ref "R4_3") (pin "2") (pinfunction "2_2") (pintype "passive"))
    )
    (net (code "87") (name "Net-(H3-VREG)") (class "Default")
      (node (ref "C11_3") (pin "1") (pinfunction "1_1") (pintype "passive"))
      (node (ref "H3") (pin "23") (pinfunction "VREG_23") (pintype "bidirectional"))
    )
    (net (code "88") (name "Net-(H4-CP)") (class "Default")
      (node (ref "C12_4") (pin "2") (pinfunction "2_2") (pintype "passive"))
      (node (ref "H4") (pin "24") (pinfunction "CP_24") (pintype "bidirectional"))
    )
    (net (code "89") (name "Net-(H4-CP1)") (class "Default")
      (node (ref "C6_4") (pin "2") (pinfunction "2_2") (pintype "passive"))
      (node (ref "H4") (pin "2") (pinfunction "CP1_2") (pintype "bidirectional"))
    )
    (net (code "90") (name "Net-(H4-CP2)") (class "Default")
      (node (ref "C6_4") (pin "1") (pinfunction "1_1") (pintype "passive"))
      (node (ref "H4") (pin "1") (pinfunction "CP2_1") (pintype "bidirectional"))
    )
    (net (code "91") (name "Net-(H4-REF)") (class "Default")
      (node (ref "C8_4") (pin "1") (pinfunction "1_1") (pintype "passive"))
      (node (ref "H4") (pin "14") (pinfunction "REF_14") (pintype "bidirectional"))
      (node (ref "R5_4") (pin "1") (pinfunction "1_1") (pintype "passive"))
      (node (ref "R6_4") (pin "1") (pinfunction "1_1") (pintype "passive"))
    )
    (net (code "92") (name "Net-(H4-ROSC)") (class "Default")
      (node (ref "H4") (pin "4") (pinfunction "ROSC_4") (pintype "bidirectional"))
      (node (ref "R4_4") (pin "2") (pinfunction "2_2") (pintype "passive"))
    )
    (net (code "93") (name "Net-(H4-VREG)") (class "Default")
      (node (ref "C11_4") (pin "1") (pinfunction "1_1") (pintype "passive"))
      (node (ref "H4") (pin "23") (pinfunction "VREG_23") (pintype "bidirectional"))
    )
    (net (code "94") (name "Net-(H5-CP)") (class "Default")
      (node (ref "C12_5") (pin "2") (pinfunction "2_2") (pintype "passive"))
      (node (ref "H5") (pin "24") (pinfunction "CP_24") (pintype "bidirectional"))
    )
    (net (code "95") (name "Net-(H5-CP1)") (class "Default")
      (node (ref "C6_5") (pin "2") (pinfunction "2_2") (pintype "passive"))
      (node (ref "H5") (pin "2") (pinfunction "CP1_2") (pintype "bidirectional"))
    )
    (net (code "96") (name "Net-(H5-CP2)") (class "Default")
      (node (ref "C6_5") (pin "1") (pinfunction "1_1") (pintype "passive"))
      (node (ref "H5") (pin "1") (pinfunction "CP2_1") (pintype "bidirectional"))
    )
    (net (code "97") (name "Net-(H5-REF)") (class "Default")
      (node (ref "C8_5") (pin "1") (pinfunction "1_1") (pintype "passive"))
      (node (ref "H5") (pin "14") (pinfunction "REF_14") (pintype "bidirectional"))
      (node (ref "R5_5") (pin "1") (pinfunction "1_1") (pintype "passive"))
      (node (ref "R6_5") (pin "1") (pinfunction "1_1") (pintype "passive"))
    )
    (net (code "98") (name "Net-(H5-ROSC)") (class "Default")
      (node (ref "H5") (pin "4") (pinfunction "ROSC_4") (pintype "bidirectional"))
      (node (ref "R4_5") (pin "2") (pinfunction "2_2") (pintype "passive"))
    )
    (net (code "99") (name "Net-(H5-VREG)") (class "Default")
      (node (ref "C11_5") (pin "1") (pinfunction "1_1") (pintype "passive"))
      (node (ref "H5") (pin "23") (pinfunction "VREG_23") (pintype "bidirectional"))
    )
    (net (code "100") (name "Net-(LED1-PadA)") (class "Default")
      (node (ref "LED1") (pin "A") (pinfunction "A_A") (pintype "passive"))
      (node (ref "R11") (pin "1") (pinfunction "1_1") (pintype "passive"))
    )
    (net (code "101") (name "Net-(LED2-PadA)") (class "Default")
      (node (ref "LED2") (pin "A") (pinfunction "A_A") (pintype "passive"))
      (node (ref "R9") (pin "1") (pinfunction "1_1") (pintype "passive"))
    )
    (net (code "102") (name "Net-(LED3-PadA)") (class "Default")
      (node (ref "LED3") (pin "A") (pinfunction "A_A") (pintype "passive"))
      (node (ref "R8") (pin "1") (pinfunction "1_1") (pintype "passive"))
    )
    (net (code "103") (name "Net-(LED4-PadA)") (class "Default")
      (node (ref "LED4") (pin "A") (pinfunction "A_A") (pintype "passive"))
      (node (ref "R14") (pin "1") (pinfunction "1_1") (pintype "passive"))
    )
    (net (code "104") (name "Net-(LED5-PadA)") (class "Default")
      (node (ref "LED5") (pin "A") (pinfunction "A_A") (pintype "passive"))
      (node (ref "R13") (pin "1") (pinfunction "1_1") (pintype "passive"))
    )
    (net (code "105") (name "Net-(LED6-PadA)") (class "Default")
      (node (ref "LED6") (pin "A") (pinfunction "A_A") (pintype "passive"))
      (node (ref "R12") (pin "1") (pinfunction "1_1") (pintype "passive"))
    )
    (net (code "106") (name "Net-(LED7-PadA)") (class "Default")
      (node (ref "LED7") (pin "A") (pinfunction "A_A") (pintype "passive"))
      (node (ref "R17") (pin "1") (pinfunction "1_1") (pintype "passive"))
    )
    (net (code "107") (name "Net-(LED8-PadA)") (class "Default")
      (node (ref "LED8") (pin "A") (pinfunction "A_A") (pintype "passive"))
      (node (ref "R16") (pin "1") (pinfunction "1_1") (pintype "passive"))
    )
    (net (code "108") (name "Net-(LED9-PadA)") (class "Default")
      (node (ref "LED9") (pin "A") (pinfunction "A_A") (pintype "passive"))
      (node (ref "R15") (pin "1") (pinfunction "1_1") (pintype "passive"))
    )
    (net (code "109") (name "Net-(LED10-PadA)") (class "Default")
      (node (ref "LED10") (pin "A") (pinfunction "A_A") (pintype "passive"))
      (node (ref "R20") (pin "1") (pinfunction "1_1") (pintype "passive"))
    )
    (net (code "110") (name "Net-(LED11-PadA)") (class "Default")
      (node (ref "LED11") (pin "A") (pinfunction "A_A") (pintype "passive"))
      (node (ref "R19") (pin "1") (pinfunction "1_1") (pintype "passive"))
    )
    (net (code "111") (name "Net-(LED12-PadA)") (class "Default")
      (node (ref "LED12") (pin "A") (pinfunction "A_A") (pintype "passive"))
      (node (ref "R18") (pin "1") (pinfunction "1_1") (pintype "passive"))
    )
    (net (code "112") (name "Net-(LED13-PadA)") (class "Default")
      (node (ref "LED13") (pin "A") (pinfunction "A_A") (pintype "passive"))
      (node (ref "R23") (pin "1") (pinfunction "1_1") (pintype "passive"))
    )
    (net (code "113") (name "Net-(LED14-PadA)") (class "Default")
      (node (ref "LED14") (pin "A") (pinfunction "A_A") (pintype "passive"))
      (node (ref "R22") (pin "1") (pinfunction "1_1") (pintype "passive"))
    )
    (net (code "114") (name "Net-(LED15-PadA)") (class "Default")
      (node (ref "LED15") (pin "A") (pinfunction "A_A") (pintype "passive"))
      (node (ref "R21") (pin "1") (pinfunction "1_1") (pintype "passive"))
    )
    (net (code "115") (name "Net-(LED16-PadA)") (class "Default")
      (node (ref "LED16") (pin "A") (pinfunction "A_A") (pintype "passive"))
      (node (ref "R26") (pin "1") (pinfunction "1_1") (pintype "passive"))
    )
    (net (code "116") (name "Net-(LED17-PadA)") (class "Default")
      (node (ref "LED17") (pin "A") (pinfunction "A_A") (pintype "passive"))
      (node (ref "R25") (pin "1") (pinfunction "1_1") (pintype "passive"))
    )
    (net (code "117") (name "Net-(LED18-PadA)") (class "Default")
      (node (ref "LED18") (pin "A") (pinfunction "A_A") (pintype "passive"))
      (node (ref "R24") (pin "1") (pinfunction "1_1") (pintype "passive"))
    )
    (net (code "118") (name "Net-(LED21-PadA)") (class "Default")
      (node (ref "LED21") (pin "A") (pinfunction "A_A") (pintype "passive"))
      (node (ref "R27") (pin "1") (pinfunction "1_1") (pintype "passive"))
    )
    (net (code "119") (name "Net-(MP-AREF)") (class "Default")
      (node (ref "C5_M") (pin "1") (pinfunction "1_1") (pintype "passive"))
      (node (ref "MP") (pin "21") (pinfunction "AREF_21") (pintype "bidirectional"))
    )
    (net (code "120") (name "Net-(MP-PC3)") (class "Default")
      (node (ref "MP") (pin "26") (pinfunction "PC3_26") (pintype "bidirectional"))
      (node (ref "MS1") (pin "P$2") (pinfunction "2_P$2") (pintype "bidirectional"))
      (node (ref "R1_M1") (pin "1") (pinfunction "1_1") (pintype "passive"))
    )
    (net (code "121") (name "Net-(MP-XTAL1)") (class "Default")
      (node (ref "C2_M") (pin "2") (pinfunction "2_2") (pintype "passive"))
      (node (ref "MP") (pin "9") (pinfunction "XTAL1_9") (pintype "bidirectional"))
      (node (ref "MX") (pin "P$2") (pinfunction "2_P$2") (pintype "passive"))
    )
    (net (code "122") (name "Net-(MP-XTAL2)") (class "Default")
      (node (ref "C3_M") (pin "2") (pinfunction "2_2") (pintype "passive"))
      (node (ref "MP") (pin "10") (pinfunction "XTAL2_10") (pintype "bidirectional"))
      (node (ref "MX") (pin "P$1") (pinfunction "1_P$1") (pintype "passive"))
    )
    (net (code "123") (name "Net-(P1-AREF)") (class "Default")
      (node (ref "C5_1") (pin "1") (pinfunction "1_1") (pintype "passive"))
      (node (ref "P1") (pin "21") (pinfunction "AREF_21") (pintype "bidirectional"))
    )
    (net (code "124") (name "Net-(P1-XTAL1)") (class "Default")
      (node (ref "C2_1") (pin "2") (pinfunction "2_2") (pintype "passive"))
      (node (ref "P1") (pin "9") (pinfunction "XTAL1_9") (pintype "bidirectional"))
      (node (ref "X1") (pin "P$2") (pinfunction "2_P$2") (pintype "passive"))
    )
    (net (code "125") (name "Net-(P1-XTAL2)") (class "Default")
      (node (ref "C3_1") (pin "2") (pinfunction "2_2") (pintype "passive"))
      (node (ref "P1") (pin "10") (pinfunction "XTAL2_10") (pintype "bidirectional"))
      (node (ref "X1") (pin "P$1") (pinfunction "1_P$1") (pintype "passive"))
    )
    (net (code "126") (name "Net-(P2-AREF)") (class "Default")
      (node (ref "C5_2") (pin "1") (pinfunction "1_1") (pintype "passive"))
      (node (ref "P2") (pin "21") (pinfunction "AREF_21") (pintype "bidirectional"))
    )
    (net (code "127") (name "Net-(P2-XTAL1)") (class "Default")
      (node (ref "C2_2") (pin "2") (pinfunction "2_2") (pintype "passive"))
      (node (ref "P2") (pin "9") (pinfunction "XTAL1_9") (pintype "bidirectional"))
      (node (ref "X2") (pin "P$2") (pinfunction "2_P$2") (pintype "passive"))
    )
    (net (code "128") (name "Net-(P2-XTAL2)") (class "Default")
      (node (ref "C3_2") (pin "2") (pinfunction "2_2") (pintype "passive"))
      (node (ref "P2") (pin "10") (pinfunction "XTAL2_10") (pintype "bidirectional"))
      (node (ref "X2") (pin "P$1") (pinfunction "1_P$1") (pintype "passive"))
    )
    (net (code "129") (name "Net-(P3-AREF)") (class "Default")
      (node (ref "C5_3") (pin "1") (pinfunction "1_1") (pintype "passive"))
      (node (ref "P3") (pin "21") (pinfunction "AREF_21") (pintype "bidirectional"))
    )
    (net (code "130") (name "Net-(P3-XTAL1)") (class "Default")
      (node (ref "C2_3") (pin "2") (pinfunction "2_2") (pintype "passive"))
      (node (ref "P3") (pin "9") (pinfunction "XTAL1_9") (pintype "bidirectional"))
      (node (ref "X3") (pin "P$2") (pinfunction "2_P$2") (pintype "passive"))
    )
    (net (code "131") (name "Net-(P3-XTAL2)") (class "Default")
      (node (ref "C3_3") (pin "2") (pinfunction "2_2") (pintype "passive"))
      (node (ref "P3") (pin "10") (pinfunction "XTAL2_10") (pintype "bidirectional"))
      (node (ref "X3") (pin "P$1") (pinfunction "1_P$1") (pintype "passive"))
    )
    (net (code "132") (name "Net-(P4-AREF)") (class "Default")
      (node (ref "C5_4") (pin "1") (pinfunction "1_1") (pintype "passive"))
      (node (ref "P4") (pin "21") (pinfunction "AREF_21") (pintype "bidirectional"))
    )
    (net (code "133") (name "Net-(P4-XTAL1)") (class "Default")
      (node (ref "C2_4") (pin "2") (pinfunction "2_2") (pintype "passive"))
      (node (ref "P4") (pin "9") (pinfunction "XTAL1_9") (pintype "bidirectional"))
      (node (ref "X4") (pin "P$2") (pinfunction "2_P$2") (pintype "passive"))
    )
    (net (code "134") (name "Net-(P4-XTAL2)") (class "Default")
      (node (ref "C3_4") (pin "2") (pinfunction "2_2") (pintype "passive"))
      (node (ref "P4") (pin "10") (pinfunction "XTAL2_10") (pintype "bidirectional"))
      (node (ref "X4") (pin "P$1") (pinfunction "1_P$1") (pintype "passive"))
    )
    (net (code "135") (name "Net-(P5-AREF)") (class "Default")
      (node (ref "C5_5") (pin "1") (pinfunction "1_1") (pintype "passive"))
      (node (ref "P5") (pin "21") (pinfunction "AREF_21") (pintype "bidirectional"))
    )
    (net (code "136") (name "Net-(P5-XTAL1)") (class "Default")
      (node (ref "C2_5") (pin "2") (pinfunction "2_2") (pintype "passive"))
      (node (ref "P5") (pin "9") (pinfunction "XTAL1_9") (pintype "bidirectional"))
      (node (ref "X5") (pin "P$2") (pinfunction "2_P$2") (pintype "passive"))
    )
    (net (code "137") (name "Net-(P5-XTAL2)") (class "Default")
      (node (ref "C3_5") (pin "2") (pinfunction "2_2") (pintype "passive"))
      (node (ref "P5") (pin "10") (pinfunction "XTAL2_10") (pintype "bidirectional"))
      (node (ref "X5") (pin "P$1") (pinfunction "1_P$1") (pintype "passive"))
    )
    (net (code "138") (name "Net-(P6-AREF)") (class "Default")
      (node (ref "C5_6") (pin "1") (pinfunction "1_1") (pintype "passive"))
      (node (ref "P6") (pin "21") (pinfunction "AREF_21") (pintype "bidirectional"))
    )
    (net (code "139") (name "Net-(P6-XTAL1)") (class "Default")
      (node (ref "C2_6") (pin "2") (pinfunction "2_2") (pintype "passive"))
      (node (ref "P6") (pin "9") (pinfunction "XTAL1_9") (pintype "bidirectional"))
      (node (ref "X6") (pin "P$2") (pinfunction "2_P$2") (pintype "passive"))
    )
    (net (code "140") (name "Net-(P6-XTAL2)") (class "Default")
      (node (ref "C3_6") (pin "2") (pinfunction "2_2") (pintype "passive"))
      (node (ref "P6") (pin "10") (pinfunction "XTAL2_10") (pintype "bidirectional"))
      (node (ref "X6") (pin "P$1") (pinfunction "1_P$1") (pintype "passive"))
    )
    (net (code "141") (name "Net-(Q3-A)") (class "Default")
      (node (ref "Q3") (pin "8") (pinfunction "A_8") (pintype "bidirectional"))
      (node (ref "R4") (pin "P$1") (pinfunction "1_P$1") (pintype "passive"))
      (node (ref "U$2") (pin "3") (pinfunction "3_3") (pintype "bidirectional"))
    )
    (net (code "142") (name "Net-(Q3-B)") (class "Default")
      (node (ref "Q3") (pin "7") (pinfunction "B_7") (pintype "bidirectional"))
      (node (ref "R4") (pin "P$2") (pinfunction "2_P$2") (pintype "passive"))
      (node (ref "U$2") (pin "6") (pinfunction "6_6") (pintype "bidirectional"))
    )
    (net (code "143") (name "Net-(Q3-Y)") (class "Default")
      (node (ref "Q3") (pin "5") (pinfunction "Y_5") (pintype "bidirectional"))
      (node (ref "R5") (pin "P$2") (pinfunction "2_P$2") (pintype "passive"))
      (node (ref "U$2") (pin "1") (pinfunction "1_1") (pintype "bidirectional"))
    )
    (net (code "144") (name "Net-(Q3-Z)") (class "Default")
      (node (ref "Q3") (pin "6") (pinfunction "Z_6") (pintype "bidirectional"))
      (node (ref "R5") (pin "P$1") (pinfunction "1_P$1") (pintype "passive"))
      (node (ref "U$2") (pin "2") (pinfunction "2_2") (pintype "bidirectional"))
    )
    (net (code "145") (name "Net-(SJ1-Pad2)") (class "Default")
      (node (ref "SJ1") (pin "2") (pinfunction "2_2") (pintype "passive"))
      (node (ref "U$2") (pin "7") (pinfunction "7_7") (pintype "bidirectional"))
      (node (ref "U$2") (pin "8") (pinfunction "8_8") (pintype "bidirectional"))
    )
    (net (code "146") (name "O1") (class "Default")
      (node (ref "JP7") (pin "2") (pinfunction "2_2") (pintype "passive"))
      (node (ref "JP8") (pin "2") (pinfunction "2_2") (pintype "passive"))
      (node (ref "Q1") (pin "2") (pinfunction "D_2") (pintype "passive"))
    )
    (net (code "147") (name "O2") (class "Default")
      (node (ref "JP7") (pin "3") (pinfunction "3_3") (pintype "passive"))
      (node (ref "JP8") (pin "3") (pinfunction "3_3") (pintype "passive"))
      (node (ref "Q2") (pin "2") (pinfunction "D_2") (pintype "passive"))
    )
    (net (code "148") (name "O3") (class "Default")
      (node (ref "JP7") (pin "4") (pinfunction "4_4") (pintype "passive"))
      (node (ref "JP8") (pin "4") (pinfunction "4_4") (pintype "passive"))
      (node (ref "Q4") (pin "2") (pinfunction "D_2") (pintype "passive"))
    )
    (net (code "149") (name "OUTA1") (class "Default")
      (node (ref "H1") (pin "16") (pinfunction "OUTA_16") (pintype "bidirectional"))
      (node (ref "JP6") (pin "2") (pinfunction "2_2") (pintype "passive"))
    )
    (net (code "150") (name "OUTA2") (class "Default")
      (node (ref "H2") (pin "16") (pinfunction "OUTA_16") (pintype "bidirectional"))
      (node (ref "JP5") (pin "2") (pinfunction "2_2") (pintype "passive"))
    )
    (net (code "151") (name "OUTA3") (class "Default")
      (node (ref "H3") (pin "16") (pinfunction "OUTA_16") (pintype "bidirectional"))
      (node (ref "JP4") (pin "2") (pinfunction "2_2") (pintype "passive"))
    )
    (net (code "152") (name "OUTA4") (class "Default")
      (node (ref "H4") (pin "16") (pinfunction "OUTA_16") (pintype "bidirectional"))
      (node (ref "JP3") (pin "2") (pinfunction "2_2") (pintype "passive"))
    )
    (net (code "153") (name "OUTA5") (class "Default")
      (node (ref "H5") (pin "16") (pinfunction "OUTA_16") (pintype "bidirectional"))
      (node (ref "JP2") (pin "2") (pinfunction "2_2") (pintype "passive"))
    )
    (net (code "154") (name "OUTB1") (class "Default")
      (node (ref "H1") (pin "21") (pinfunction "OUTB_21") (pintype "bidirectional"))
      (node (ref "JP6") (pin "1") (pinfunction "1_1") (pintype "passive"))
    )
    (net (code "155") (name "OUTB2") (class "Default")
      (node (ref "H2") (pin "21") (pinfunction "OUTB_21") (pintype "bidirectional"))
      (node (ref "JP5") (pin "1") (pinfunction "1_1") (pintype "passive"))
    )
    (net (code "156") (name "OUTB3") (class "Default")
      (node (ref "H3") (pin "21") (pinfunction "OUTB_21") (pintype "bidirectional"))
      (node (ref "JP4") (pin "1") (pinfunction "1_1") (pintype "passive"))
    )
    (net (code "157") (name "OUTB4") (class "Default")
      (node (ref "H4") (pin "21") (pinfunction "OUTB_21") (pintype "bidirectional"))
      (node (ref "JP3") (pin "1") (pinfunction "1_1") (pintype "passive"))
    )
    (net (code "158") (name "OUTB5") (class "Default")
      (node (ref "H5") (pin "21") (pinfunction "OUTB_21") (pintype "bidirectional"))
      (node (ref "JP2") (pin "1") (pinfunction "1_1") (pintype "passive"))
    )
    (net (code "159") (name "PFD1_1") (class "Default")
      (node (ref "H1") (pin "13") (pinfunction "PFD1_13") (pintype "bidirectional"))
      (node (ref "P1") (pin "14") (pinfunction "PB0_14") (pintype "bidirectional"))
    )
    (net (code "160") (name "PFD1_2") (class "Default")
      (node (ref "H2") (pin "13") (pinfunction "PFD1_13") (pintype "bidirectional"))
      (node (ref "P2") (pin "14") (pinfunction "PB0_14") (pintype "bidirectional"))
    )
    (net (code "161") (name "PFD1_3") (class "Default")
      (node (ref "H3") (pin "13") (pinfunction "PFD1_13") (pintype "bidirectional"))
      (node (ref "P3") (pin "14") (pinfunction "PB0_14") (pintype "bidirectional"))
    )
    (net (code "162") (name "PFD1_4") (class "Default")
      (node (ref "H4") (pin "13") (pinfunction "PFD1_13") (pintype "bidirectional"))
      (node (ref "P4") (pin "14") (pinfunction "PB0_14") (pintype "bidirectional"))
    )
    (net (code "163") (name "PFD1_5") (class "Default")
      (node (ref "H5") (pin "13") (pinfunction "PFD1_13") (pintype "bidirectional"))
      (node (ref "P5") (pin "14") (pinfunction "PB0_14") (pintype "bidirectional"))
    )
    (net (code "164") (name "PFD2_1") (class "Default")
      (node (ref "H1") (pin "11") (pinfunction "PFD2_11") (pintype "bidirectional"))
      (node (ref "P1") (pin "18") (pinfunction "PB4_18") (pintype "bidirectional"))
    )
    (net (code "165") (name "PFD2_2") (class "Default")
      (node (ref "H2") (pin "11") (pinfunction "PFD2_11") (pintype "bidirectional"))
      (node (ref "P2") (pin "18") (pinfunction "PB4_18") (pintype "bidirectional"))
    )
    (net (code "166") (name "PFD2_3") (class "Default")
      (node (ref "H3") (pin "11") (pinfunction "PFD2_11") (pintype "bidirectional"))
      (node (ref "P3") (pin "18") (pinfunction "PB4_18") (pintype "bidirectional"))
    )
    (net (code "167") (name "PFD2_4") (class "Default")
      (node (ref "H4") (pin "11") (pinfunction "PFD2_11") (pintype "bidirectional"))
      (node (ref "P4") (pin "18") (pinfunction "PB4_18") (pintype "bidirectional"))
    )
    (net (code "168") (name "PFD2_5") (class "Default")
      (node (ref "H5") (pin "11") (pinfunction "PFD2_11") (pintype "bidirectional"))
      (node (ref "P5") (pin "18") (pinfunction "PB4_18") (pintype "bidirectional"))
    )
    (net (code "169") (name "PHASE1") (class "Default")
      (node (ref "H1") (pin "3") (pinfunction "PHASE_3") (pintype "bidirectional"))
      (node (ref "P1") (pin "23") (pinfunction "PC0_23") (pintype "bidirectional"))
    )
    (net (code "170") (name "PHASE2") (class "Default")
      (node (ref "H2") (pin "3") (pinfunction "PHASE_3") (pintype "bidirectional"))
      (node (ref "P2") (pin "23") (pinfunction "PC0_23") (pintype "bidirectional"))
    )
    (net (code "171") (name "PHASE3") (class "Default")
      (node (ref "H3") (pin "3") (pinfunction "PHASE_3") (pintype "bidirectional"))
      (node (ref "P3") (pin "23") (pinfunction "PC0_23") (pintype "bidirectional"))
    )
    (net (code "172") (name "PHASE4") (class "Default")
      (node (ref "H4") (pin "3") (pinfunction "PHASE_3") (pintype "bidirectional"))
      (node (ref "P4") (pin "23") (pinfunction "PC0_23") (pintype "bidirectional"))
    )
    (net (code "173") (name "PHASE5") (class "Default")
      (node (ref "H5") (pin "3") (pinfunction "PHASE_3") (pintype "bidirectional"))
      (node (ref "P5") (pin "23") (pinfunction "PC0_23") (pintype "bidirectional"))
    )
    (net (code "174") (name "PULSE1") (class "Default")
      (node (ref "P1") (pin "11") (pinfunction "PD5_11") (pintype "bidirectional"))
      (node (ref "R8_1") (pin "2") (pinfunction "2_2") (pintype "passive"))
      (node (ref "R9_1") (pin "2") (pinfunction "2_2") (pintype "passive"))
    )
    (net (code "175") (name "PULSE2") (class "Default")
      (node (ref "P2") (pin "11") (pinfunction "PD5_11") (pintype "bidirectional"))
      (node (ref "R8_2") (pin "2") (pinfunction "2_2") (pintype "passive"))
      (node (ref "R9_2") (pin "2") (pinfunction "2_2") (pintype "passive"))
    )
    (net (code "176") (name "PULSE3") (class "Default")
      (node (ref "P3") (pin "11") (pinfunction "PD5_11") (pintype "bidirectional"))
      (node (ref "R8_3") (pin "2") (pinfunction "2_2") (pintype "passive"))
      (node (ref "R9_3") (pin "2") (pinfunction "2_2") (pintype "passive"))
    )
    (net (code "177") (name "PULSE4") (class "Default")
      (node (ref "P4") (pin "11") (pinfunction "PD5_11") (pintype "bidirectional"))
      (node (ref "R8_4") (pin "2") (pinfunction "2_2") (pintype "passive"))
      (node (ref "R9_4") (pin "2") (pinfunction "2_2") (pintype "passive"))
    )
    (net (code "178") (name "PULSE5") (class "Default")
      (node (ref "P5") (pin "11") (pinfunction "PD5_11") (pintype "bidirectional"))
      (node (ref "R8_5") (pin "2") (pinfunction "2_2") (pintype "passive"))
      (node (ref "R9_5") (pin "2") (pinfunction "2_2") (pintype "passive"))
    )
    (net (code "179") (name "PWM1") (class "Default")
      (node (ref "JP15") (pin "3") (pinfunction "3_3") (pintype "passive"))
      (node (ref "MP") (pin "11") (pinfunction "PD5_11") (pintype "bidirectional"))
    )
    (net (code "180") (name "PWM2") (class "Default")
      (node (ref "JP14") (pin "3") (pinfunction "3_3") (pintype "passive"))
      (node (ref "MP") (pin "12") (pinfunction "PD6_12") (pintype "bidirectional"))
    )
    (net (code "181") (name "R1") (class "Default")
      (node (ref "P1") (pin "2") (pinfunction "PD0_2") (pintype "bidirectional"))
    )
    (net (code "182") (name "R2") (class "Default")
      (node (ref "P2") (pin "2") (pinfunction "PD0_2") (pintype "bidirectional"))
    )
    (net (code "183") (name "R3") (class "Default")
      (node (ref "P3") (pin "2") (pinfunction "PD0_2") (pintype "bidirectional"))
    )
    (net (code "184") (name "R4") (class "Default")
      (node (ref "P4") (pin "2") (pinfunction "PD0_2") (pintype "bidirectional"))
    )
    (net (code "185") (name "R5") (class "Default")
      (node (ref "P5") (pin "2") (pinfunction "PD0_2") (pintype "bidirectional"))
    )
    (net (code "186") (name "R7") (class "Default")
      (node (ref "P6") (pin "2") (pinfunction "PD0_2") (pintype "bidirectional"))
    )
    (net (code "187") (name "REF1_1") (class "Default")
      (node (ref "P1") (pin "15") (pinfunction "PB1_15") (pintype "bidirectional"))
      (node (ref "R5_1") (pin "2") (pinfunction "2_2") (pintype "passive"))
    )
    (net (code "188") (name "REF1_2") (class "Default")
      (node (ref "P2") (pin "15") (pinfunction "PB1_15") (pintype "bidirectional"))
      (node (ref "R5_2") (pin "2") (pinfunction "2_2") (pintype "passive"))
    )
    (net (code "189") (name "REF1_3") (class "Default")
      (node (ref "P3") (pin "15") (pinfunction "PB1_15") (pintype "bidirectional"))
      (node (ref "R5_3") (pin "2") (pinfunction "2_2") (pintype "passive"))
    )
    (net (code "190") (name "REF1_4") (class "Default")
      (node (ref "P4") (pin "15") (pinfunction "PB1_15") (pintype "bidirectional"))
      (node (ref "R5_4") (pin "2") (pinfunction "2_2") (pintype "passive"))
    )
    (net (code "191") (name "REF1_5") (class "Default")
      (node (ref "P5") (pin "15") (pinfunction "PB1_15") (pintype "bidirectional"))
      (node (ref "R5_5") (pin "2") (pinfunction "2_2") (pintype "passive"))
    )
    (net (code "192") (name "RM") (class "Default")
      (node (ref "MD") (pin "3") (pinfunction "3_3") (pintype "passive"))
      (node (ref "MP") (pin "2") (pinfunction "PD0_2") (pintype "bidirectional"))
      (node (ref "Q3") (pin "2") (pinfunction "R_2") (pintype "bidirectional"))
    )
    (net (code "193") (name "S1") (class "Default")
      (node (ref "MP") (pin "15") (pinfunction "PB1_15") (pintype "bidirectional"))
      (node (ref "Q1") (pin "1") (pinfunction "G_1") (pintype "passive"))
      (node (ref "R3") (pin "P$2") (pinfunction "2_P$2") (pintype "passive"))
    )
    (net (code "194") (name "S2") (class "Default")
      (node (ref "MP") (pin "16") (pinfunction "PB2_16") (pintype "bidirectional"))
      (node (ref "Q2") (pin "1") (pinfunction "G_1") (pintype "passive"))
      (node (ref "R6") (pin "P$2") (pinfunction "2_P$2") (pintype "passive"))
    )
    (net (code "195") (name "S3") (class "Default")
      (node (ref "MP") (pin "17") (pinfunction "PB3_17") (pintype "bidirectional"))
      (node (ref "Q4") (pin "1") (pinfunction "G_1") (pintype "passive"))
      (node (ref "R7") (pin "P$2") (pinfunction "2_P$2") (pintype "passive"))
    )
    (net (code "196") (name "S6") (class "Default")
      (node (ref "J6") (pin "P$2") (pinfunction "2_P$2") (pintype "bidirectional"))
      (node (ref "P6") (pin "1") (pinfunction "PC6_1") (pintype "bidirectional"))
      (node (ref "R1_6") (pin "1") (pinfunction "1_1") (pintype "passive"))
      (node (ref "R26") (pin "2") (pinfunction "2_2") (pintype "passive"))
    )
    (net (code "197") (name "SCL") (class "Default")
      (node (ref "MP") (pin "28") (pinfunction "PC5_28") (pintype "bidirectional"))
      (node (ref "P1") (pin "28") (pinfunction "PC5_28") (pintype "bidirectional"))
      (node (ref "P2") (pin "28") (pinfunction "PC5_28") (pintype "bidirectional"))
      (node (ref "P3") (pin "28") (pinfunction "PC5_28") (pintype "bidirectional"))
      (node (ref "P4") (pin "28") (pinfunction "PC5_28") (pintype "bidirectional"))
      (node (ref "P5") (pin "28") (pinfunction "PC5_28") (pintype "bidirectional"))
      (node (ref "P6") (pin "28") (pinfunction "PC5_28") (pintype "bidirectional"))
      (node (ref "R1") (pin "P$2") (pinfunction "2_P$2") (pintype "passive"))
    )
    (net (code "198") (name "SD6") (class "Default")
      (node (ref "P6") (pin "5") (pinfunction "PD3_5") (pintype "bidirectional"))
      (node (ref "U$26") (pin "4") (pinfunction "DI_4") (pintype "bidirectional"))
    )
    (net (code "199") (name "SDA") (class "Default")
      (node (ref "MP") (pin "27") (pinfunction "PC4_27") (pintype "bidirectional"))
      (node (ref "P1") (pin "27") (pinfunction "PC4_27") (pintype "bidirectional"))
      (node (ref "P2") (pin "27") (pinfunction "PC4_27") (pintype "bidirectional"))
      (node (ref "P3") (pin "27") (pinfunction "PC4_27") (pintype "bidirectional"))
      (node (ref "P4") (pin "27") (pinfunction "PC4_27") (pintype "bidirectional"))
      (node (ref "P5") (pin "27") (pinfunction "PC4_27") (pintype "bidirectional"))
      (node (ref "P6") (pin "27") (pinfunction "PC4_27") (pintype "bidirectional"))
      (node (ref "R2") (pin "P$2") (pinfunction "2_P$2") (pintype "passive"))
    )
    (net (code "200") (name "SLEEP1_1") (class "Default")
      (node (ref "H1") (pin "22") (pinfunction "SLEEP_22") (pintype "bidirectional"))
      (node (ref "P1") (pin "24") (pinfunction "PC1_24") (pintype "bidirectional"))
    )
    (net (code "201") (name "SLEEP1_2") (class "Default")
      (node (ref "H2") (pin "22") (pinfunction "SLEEP_22") (pintype "bidirectional"))
      (node (ref "P2") (pin "24") (pinfunction "PC1_24") (pintype "bidirectional"))
    )
    (net (code "202") (name "SLEEP1_3") (class "Default")
      (node (ref "H3") (pin "22") (pinfunction "SLEEP_22") (pintype "bidirectional"))
      (node (ref "P3") (pin "24") (pinfunction "PC1_24") (pintype "bidirectional"))
    )
    (net (code "203") (name "SLEEP1_4") (class "Default")
      (node (ref "H4") (pin "22") (pinfunction "SLEEP_22") (pintype "bidirectional"))
      (node (ref "P4") (pin "24") (pinfunction "PC1_24") (pintype "bidirectional"))
    )
    (net (code "204") (name "SLEEP1_5") (class "Default")
      (node (ref "H5") (pin "22") (pinfunction "SLEEP_22") (pintype "bidirectional"))
      (node (ref "P5") (pin "24") (pinfunction "PC1_24") (pintype "bidirectional"))
    )
    (net (code "205") (name "SR6") (class "Default")
      (node (ref "P6") (pin "4") (pinfunction "PD2_4") (pintype "bidirectional"))
      (node (ref "U$26") (pin "1") (pinfunction "RO_1") (pintype "bidirectional"))
    )
    (net (code "206") (name "V5") (class "Default")
      (node (ref "C10") (pin "1") (pinfunction "1_1") (pintype "passive"))
      (node (ref "C1_1") (pin "2") (pinfunction "2_2") (pintype "passive"))
      (node (ref "C1_2") (pin "2") (pinfunction "2_2") (pintype "passive"))
      (node (ref "C1_3") (pin "2") (pinfunction "2_2") (pintype "passive"))
      (node (ref "C1_4") (pin "2") (pinfunction "2_2") (pintype "passive"))
      (node (ref "C1_5") (pin "2") (pinfunction "2_2") (pintype "passive"))
      (node (ref "C1_6") (pin "2") (pinfunction "2_2") (pintype "passive"))
      (node (ref "C1_M") (pin "2") (pinfunction "2_2") (pintype "passive"))
      (node (ref "C4_1") (pin "1") (pinfunction "1_1") (pintype "passive"))
      (node (ref "C4_2") (pin "1") (pinfunction "1_1") (pintype "passive"))
      (node (ref "C4_3") (pin "1") (pinfunction "1_1") (pintype "passive"))
      (node (ref "C4_4") (pin "1") (pinfunction "1_1") (pintype "passive"))
      (node (ref "C4_5") (pin "1") (pinfunction "1_1") (pintype "passive"))
      (node (ref "C4_6") (pin "1") (pinfunction "1_1") (pintype "passive"))
      (node (ref "C4_M") (pin "1") (pinfunction "1_1") (pintype "passive"))
      (node (ref "C7_1") (pin "1") (pinfunction "1_1") (pintype "passive"))
      (node (ref "C7_2") (pin "1") (pinfunction "1_1") (pintype "passive"))
      (node (ref "C7_3") (pin "1") (pinfunction "1_1") (pintype "passive"))
      (node (ref "C7_4") (pin "1") (pinfunction "1_1") (pintype "passive"))
      (node (ref "C7_5") (pin "1") (pinfunction "1_1") (pintype "passive"))
      (node (ref "CV4") (pin "1") (pinfunction "1_1") (pintype "passive"))
      (node (ref "E1") (pin "4") (pinfunction "4_4") (pintype "passive"))
      (node (ref "E2") (pin "4") (pinfunction "4_4") (pintype "passive"))
      (node (ref "E3") (pin "4") (pinfunction "4_4") (pintype "passive"))
      (node (ref "E4") (pin "4") (pinfunction "4_4") (pintype "passive"))
      (node (ref "E5") (pin "4") (pinfunction "4_4") (pintype "passive"))
      (node (ref "H1") (pin "9") (pinfunction "VDD_9") (pintype "bidirectional"))
      (node (ref "H2") (pin "9") (pinfunction "VDD_9") (pintype "bidirectional"))
      (node (ref "H3") (pin "9") (pinfunction "VDD_9") (pintype "bidirectional"))
      (node (ref "H4") (pin "9") (pinfunction "VDD_9") (pintype "bidirectional"))
      (node (ref "H5") (pin "9") (pinfunction "VDD_9") (pintype "bidirectional"))
      (node (ref "JP10") (pin "1") (pinfunction "1_1") (pintype "passive"))
      (node (ref "JP11") (pin "1") (pinfunction "1_1") (pintype "passive"))
      (node (ref "JP12") (pin "1") (pinfunction "1_1") (pintype "passive"))
      (node (ref "JP13") (pin "1") (pinfunction "1_1") (pintype "passive"))
      (node (ref "JP14") (pin "2") (pinfunction "2_2") (pintype "passive"))
      (node (ref "JP15") (pin "2") (pinfunction "2_2") (pintype "passive"))
      (node (ref "JP9") (pin "1") (pinfunction "1_1") (pintype "passive"))
      (node (ref "MP") (pin "20") (pinfunction "AVCC_20") (pintype "bidirectional"))
      (node (ref "MP") (pin "7") (pinfunction "VCC_7") (pintype "bidirectional"))
      (node (ref "P1") (pin "20") (pinfunction "AVCC_20") (pintype "bidirectional"))
      (node (ref "P1") (pin "7") (pinfunction "VCC_7") (pintype "bidirectional"))
      (node (ref "P2") (pin "20") (pinfunction "AVCC_20") (pintype "bidirectional"))
      (node (ref "P2") (pin "7") (pinfunction "VCC_7") (pintype "bidirectional"))
      (node (ref "P3") (pin "20") (pinfunction "AVCC_20") (pintype "bidirectional"))
      (node (ref "P3") (pin "7") (pinfunction "VCC_7") (pintype "bidirectional"))
      (node (ref "P4") (pin "20") (pinfunction "AVCC_20") (pintype "bidirectional"))
      (node (ref "P4") (pin "7") (pinfunction "VCC_7") (pintype "bidirectional"))
      (node (ref "P5") (pin "20") (pinfunction "AVCC_20") (pintype "bidirectional"))
      (node (ref "P5") (pin "7") (pinfunction "VCC_7") (pintype "bidirectional"))
      (node (ref "P6") (pin "20") (pinfunction "AVCC_20") (pintype "bidirectional"))
      (node (ref "P6") (pin "7") (pinfunction "VCC_7") (pintype "bidirectional"))
      (node (ref "Q3") (pin "1") (pinfunction "VCC_1") (pintype "bidirectional"))
      (node (ref "Q5") (pin "3") (pinfunction "VOUT_3") (pintype "bidirectional"))
      (node (ref "R1") (pin "P$1") (pinfunction "1_P$1") (pintype "passive"))
      (node (ref "R1_1") (pin "2") (pinfunction "2_2") (pintype "passive"))
      (node (ref "R1_2") (pin "2") (pinfunction "2_2") (pintype "passive"))
      (node (ref "R1_3") (pin "2") (pinfunction "2_2") (pintype "passive"))
      (node (ref "R1_4") (pin "2") (pinfunction "2_2") (pintype "passive"))
      (node (ref "R1_5") (pin "2") (pinfunction "2_2") (pintype "passive"))
      (node (ref "R1_6") (pin "2") (pinfunction "2_2") (pintype "passive"))
      (node (ref "R1_M") (pin "2") (pinfunction "2_2") (pintype "passive"))
      (node (ref "R1_M1") (pin "2") (pinfunction "2_2") (pintype "passive"))
      (node (ref "R2") (pin "P$1") (pinfunction "1_P$1") (pintype "passive"))
      (node (ref "R4_1") (pin "1") (pinfunction "1_1") (pintype "passive"))
      (node (ref "R4_2") (pin "1") (pinfunction "1_1") (pintype "passive"))
      (node (ref "R4_3") (pin "1") (pinfunction "1_1") (pintype "passive"))
      (node (ref "R4_4") (pin "1") (pinfunction "1_1") (pintype "passive"))
      (node (ref "R4_5") (pin "1") (pinfunction "1_1") (pintype "passive"))
      (node (ref "U$26") (pin "8") (pinfunction "VCC_8") (pintype "bidirectional"))
    )
    (net (code "207") (name "VIN") (class "Default")
      (node (ref "C10_1") (pin "2") (pinfunction "2_2") (pintype "passive"))
      (node (ref "C10_2") (pin "2") (pinfunction "2_2") (pintype "passive"))
      (node (ref "C10_3") (pin "2") (pinfunction "2_2") (pintype "passive"))
      (node (ref "C10_4") (pin "2") (pinfunction "2_2") (pintype "passive"))
      (node (ref "C10_5") (pin "2") (pinfunction "2_2") (pintype "passive"))
      (node (ref "CV3") (pin "1") (pinfunction "1_1") (pintype "passive"))
      (node (ref "H1") (pin "20") (pinfunction "VBB_20") (pintype "bidirectional"))
      (node (ref "H2") (pin "20") (pinfunction "VBB_20") (pintype "bidirectional"))
      (node (ref "H3") (pin "20") (pinfunction "VBB_20") (pintype "bidirectional"))
      (node (ref "H4") (pin "20") (pinfunction "VBB_20") (pintype "bidirectional"))
      (node (ref "H5") (pin "20") (pinfunction "VBB_20") (pintype "bidirectional"))
      (node (ref "JP1") (pin "1") (pinfunction "1_1") (pintype "passive"))
      (node (ref "JP7") (pin "1") (pinfunction "1_1") (pintype "passive"))
      (node (ref "JP8") (pin "1") (pinfunction "1_1") (pintype "passive"))
      (node (ref "O6") (pin "2") (pinfunction "2_2") (pintype "passive"))
      (node (ref "Q5") (pin "1") (pinfunction "VIN_1") (pintype "bidirectional"))
    )
    (net (code "208") (name "unconnected-(MP-PB4-Pad18)") (class "Default")
      (node (ref "MP") (pin "18") (pinfunction "PB4_18") (pintype "bidirectional"))
    )
    (net (code "209") (name "unconnected-(MP-PB5-Pad19)") (class "Default")
      (node (ref "MP") (pin "19") (pinfunction "PB5_19") (pintype "bidirectional"))
    )
    (net (code "210") (name "unconnected-(MP-PC0-Pad23)") (class "Default")
      (node (ref "MP") (pin "23") (pinfunction "PC0_23") (pintype "bidirectional"))
    )
    (net (code "211") (name "unconnected-(MP-PC1-Pad24)") (class "Default")
      (node (ref "MP") (pin "24") (pinfunction "PC1_24") (pintype "bidirectional"))
    )
    (net (code "212") (name "unconnected-(MP-PC2-Pad25)") (class "Default")
      (node (ref "MP") (pin "25") (pinfunction "PC2_25") (pintype "bidirectional"))
    )
    (net (code "213") (name "unconnected-(P1-PC2-Pad25)") (class "Default")
      (node (ref "P1") (pin "25") (pinfunction "PC2_25") (pintype "bidirectional"))
    )
    (net (code "214") (name "unconnected-(P1-PD4-Pad6)") (class "Default")
      (node (ref "P1") (pin "6") (pinfunction "PD4_6") (pintype "bidirectional"))
    )
    (net (code "215") (name "unconnected-(P2-PC2-Pad25)") (class "Default")
      (node (ref "P2") (pin "25") (pinfunction "PC2_25") (pintype "bidirectional"))
    )
    (net (code "216") (name "unconnected-(P2-PD4-Pad6)") (class "Default")
      (node (ref "P2") (pin "6") (pinfunction "PD4_6") (pintype "bidirectional"))
    )
    (net (code "217") (name "unconnected-(P3-PC2-Pad25)") (class "Default")
      (node (ref "P3") (pin "25") (pinfunction "PC2_25") (pintype "bidirectional"))
    )
    (net (code "218") (name "unconnected-(P3-PD4-Pad6)") (class "Default")
      (node (ref "P3") (pin "6") (pinfunction "PD4_6") (pintype "bidirectional"))
    )
    (net (code "219") (name "unconnected-(P4-PC2-Pad25)") (class "Default")
      (node (ref "P4") (pin "25") (pinfunction "PC2_25") (pintype "bidirectional"))
    )
    (net (code "220") (name "unconnected-(P4-PD4-Pad6)") (class "Default")
      (node (ref "P4") (pin "6") (pinfunction "PD4_6") (pintype "bidirectional"))
    )
    (net (code "221") (name "unconnected-(P5-PC2-Pad25)") (class "Default")
      (node (ref "P5") (pin "25") (pinfunction "PC2_25") (pintype "bidirectional"))
    )
    (net (code "222") (name "unconnected-(P5-PD4-Pad6)") (class "Default")
      (node (ref "P5") (pin "6") (pinfunction "PD4_6") (pintype "bidirectional"))
    )
    (net (code "223") (name "unconnected-(P6-PB0-Pad14)") (class "Default")
      (node (ref "P6") (pin "14") (pinfunction "PB0_14") (pintype "bidirectional"))
    )
    (net (code "224") (name "unconnected-(P6-PB1-Pad15)") (class "Default")
      (node (ref "P6") (pin "15") (pinfunction "PB1_15") (pintype "bidirectional"))
    )
    (net (code "225") (name "unconnected-(P6-PB2-Pad16)") (class "Default")
      (node (ref "P6") (pin "16") (pinfunction "PB2_16") (pintype "bidirectional"))
    )
    (net (code "226") (name "unconnected-(P6-PB3-Pad17)") (class "Default")
      (node (ref "P6") (pin "17") (pinfunction "PB3_17") (pintype "bidirectional"))
    )
    (net (code "227") (name "unconnected-(P6-PB4-Pad18)") (class "Default")
      (node (ref "P6") (pin "18") (pinfunction "PB4_18") (pintype "bidirectional"))
    )
    (net (code "228") (name "unconnected-(P6-PB5-Pad19)") (class "Default")
      (node (ref "P6") (pin "19") (pinfunction "PB5_19") (pintype "bidirectional"))
    )
    (net (code "229") (name "unconnected-(P6-PC0-Pad23)") (class "Default")
      (node (ref "P6") (pin "23") (pinfunction "PC0_23") (pintype "bidirectional"))
    )
    (net (code "230") (name "unconnected-(P6-PC1-Pad24)") (class "Default")
      (node (ref "P6") (pin "24") (pinfunction "PC1_24") (pintype "bidirectional"))
    )
    (net (code "231") (name "unconnected-(P6-PC2-Pad25)") (class "Default")
      (node (ref "P6") (pin "25") (pinfunction "PC2_25") (pintype "bidirectional"))
    )
    (net (code "232") (name "unconnected-(P6-PC3-Pad26)") (class "Default")
      (node (ref "P6") (pin "26") (pinfunction "PC3_26") (pintype "bidirectional"))
    )
    (net (code "233") (name "unconnected-(P6-PD5-Pad11)") (class "Default")
      (node (ref "P6") (pin "11") (pinfunction "PD5_11") (pintype "bidirectional"))
    )
    (net (code "234") (name "unconnected-(U$2-Pad4)") (class "Default")
      (node (ref "U$2") (pin "4") (pinfunction "4_4") (pintype "bidirectional"))
    )
    (net (code "235") (name "unconnected-(U$2-Pad5)") (class "Default")
      (node (ref "U$2") (pin "5") (pinfunction "5_5") (pintype "bidirectional"))
    )
  )
)
